# Schematic_SF_1_12_2020_V10.net
KiCad netlist of a schematic drawn in EAGLE
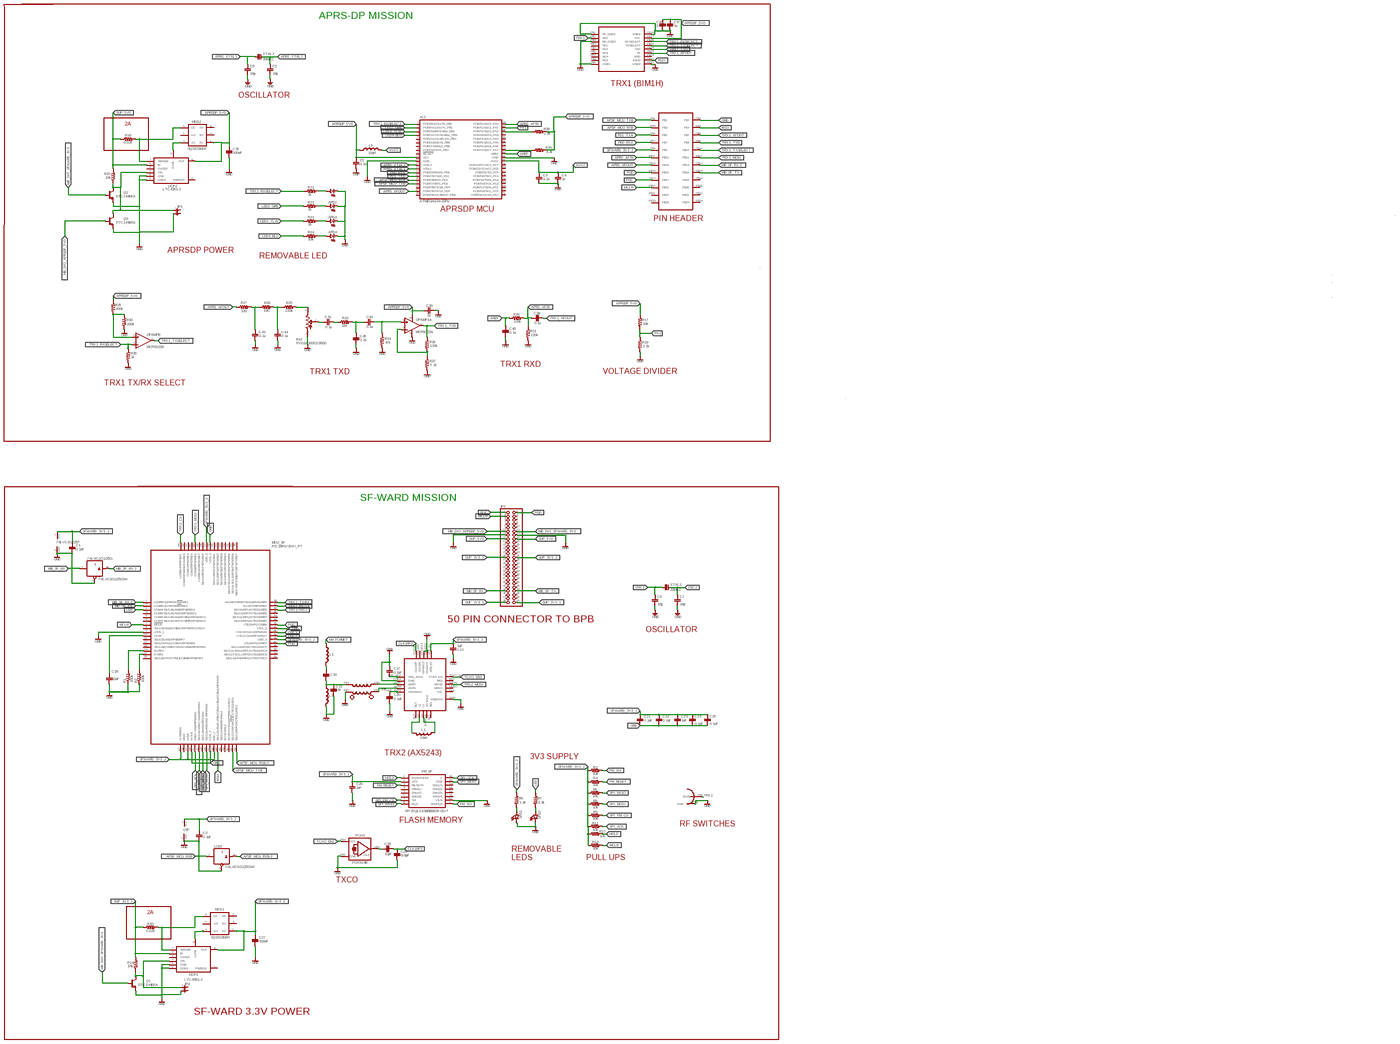
[diagram p0: schematic, sheet 1, overview]
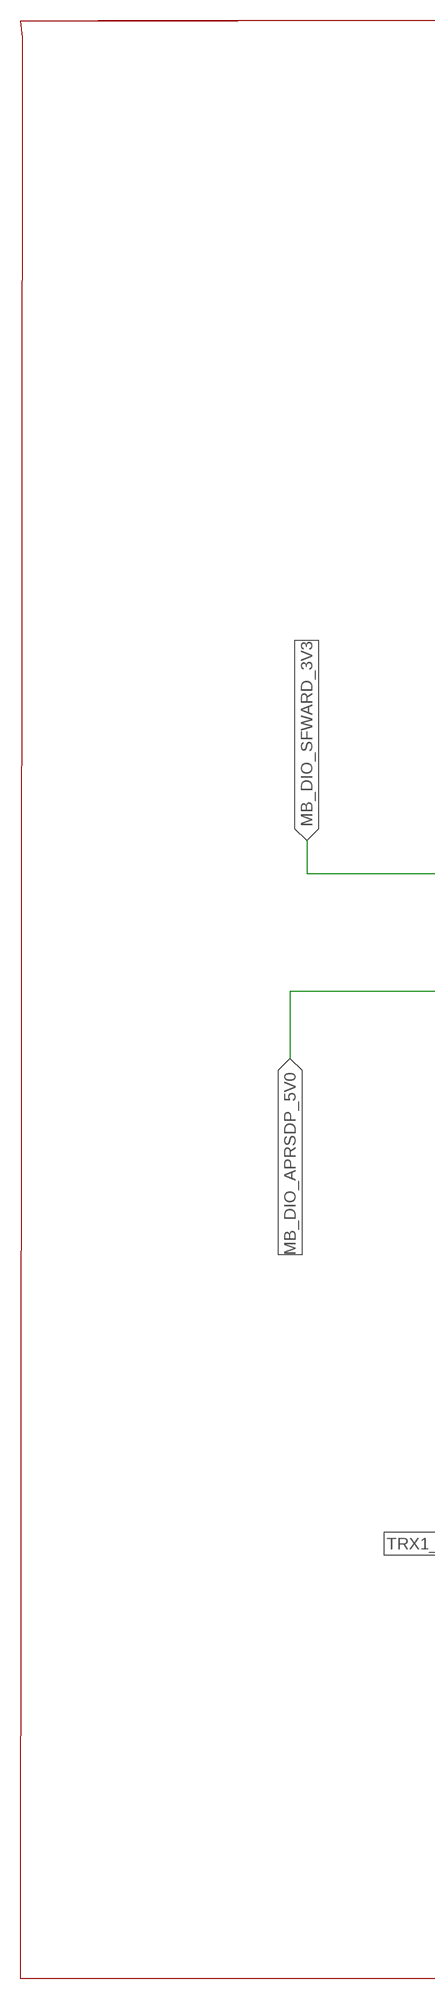
[diagram p1: schematic, sheet 1, part 1 of 4]
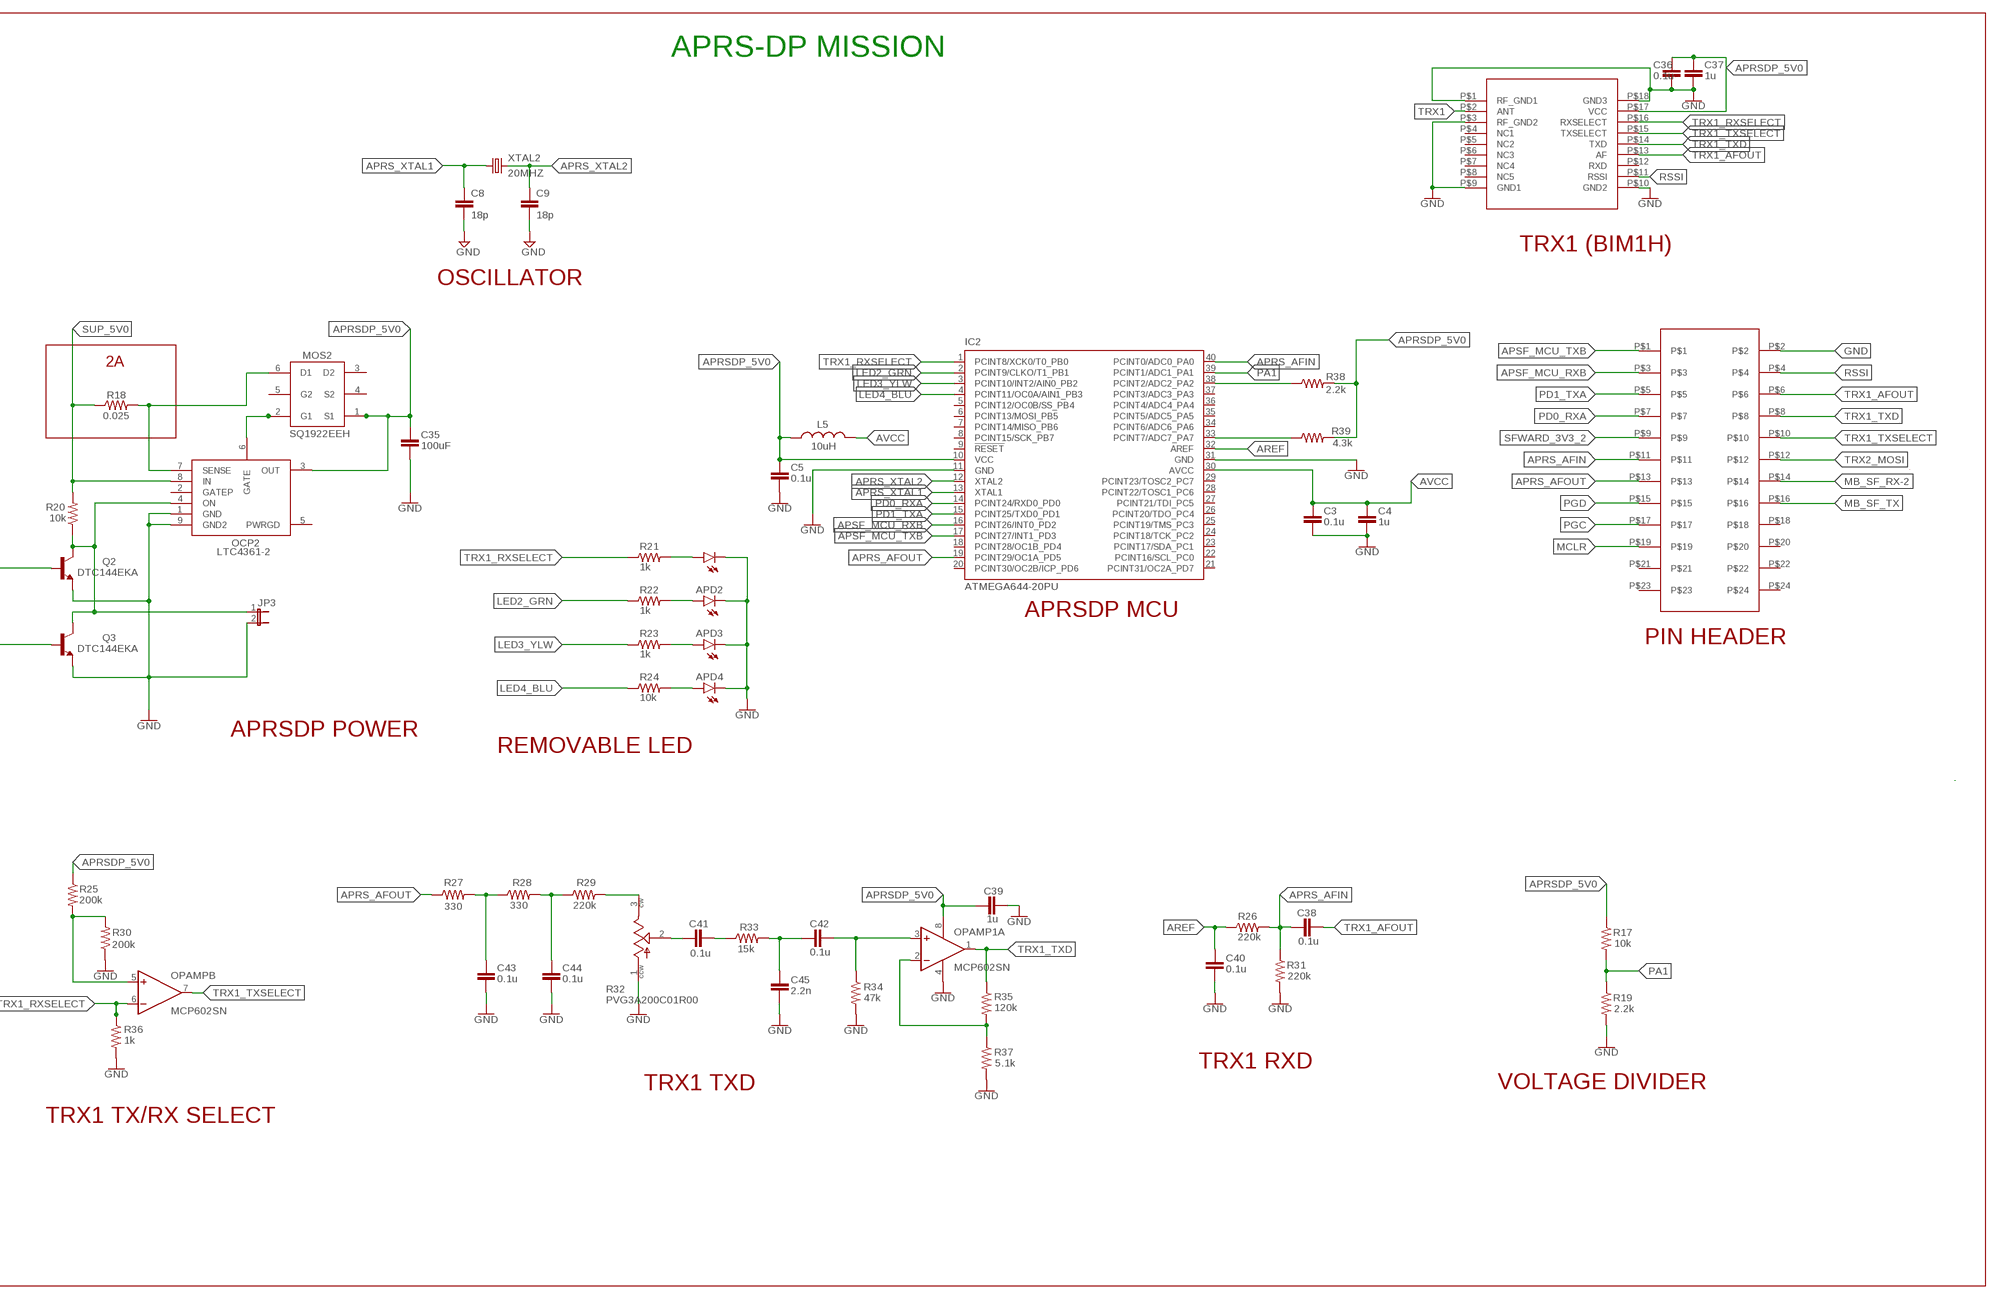
[diagram p2: schematic, sheet 1, part 2 of 4]
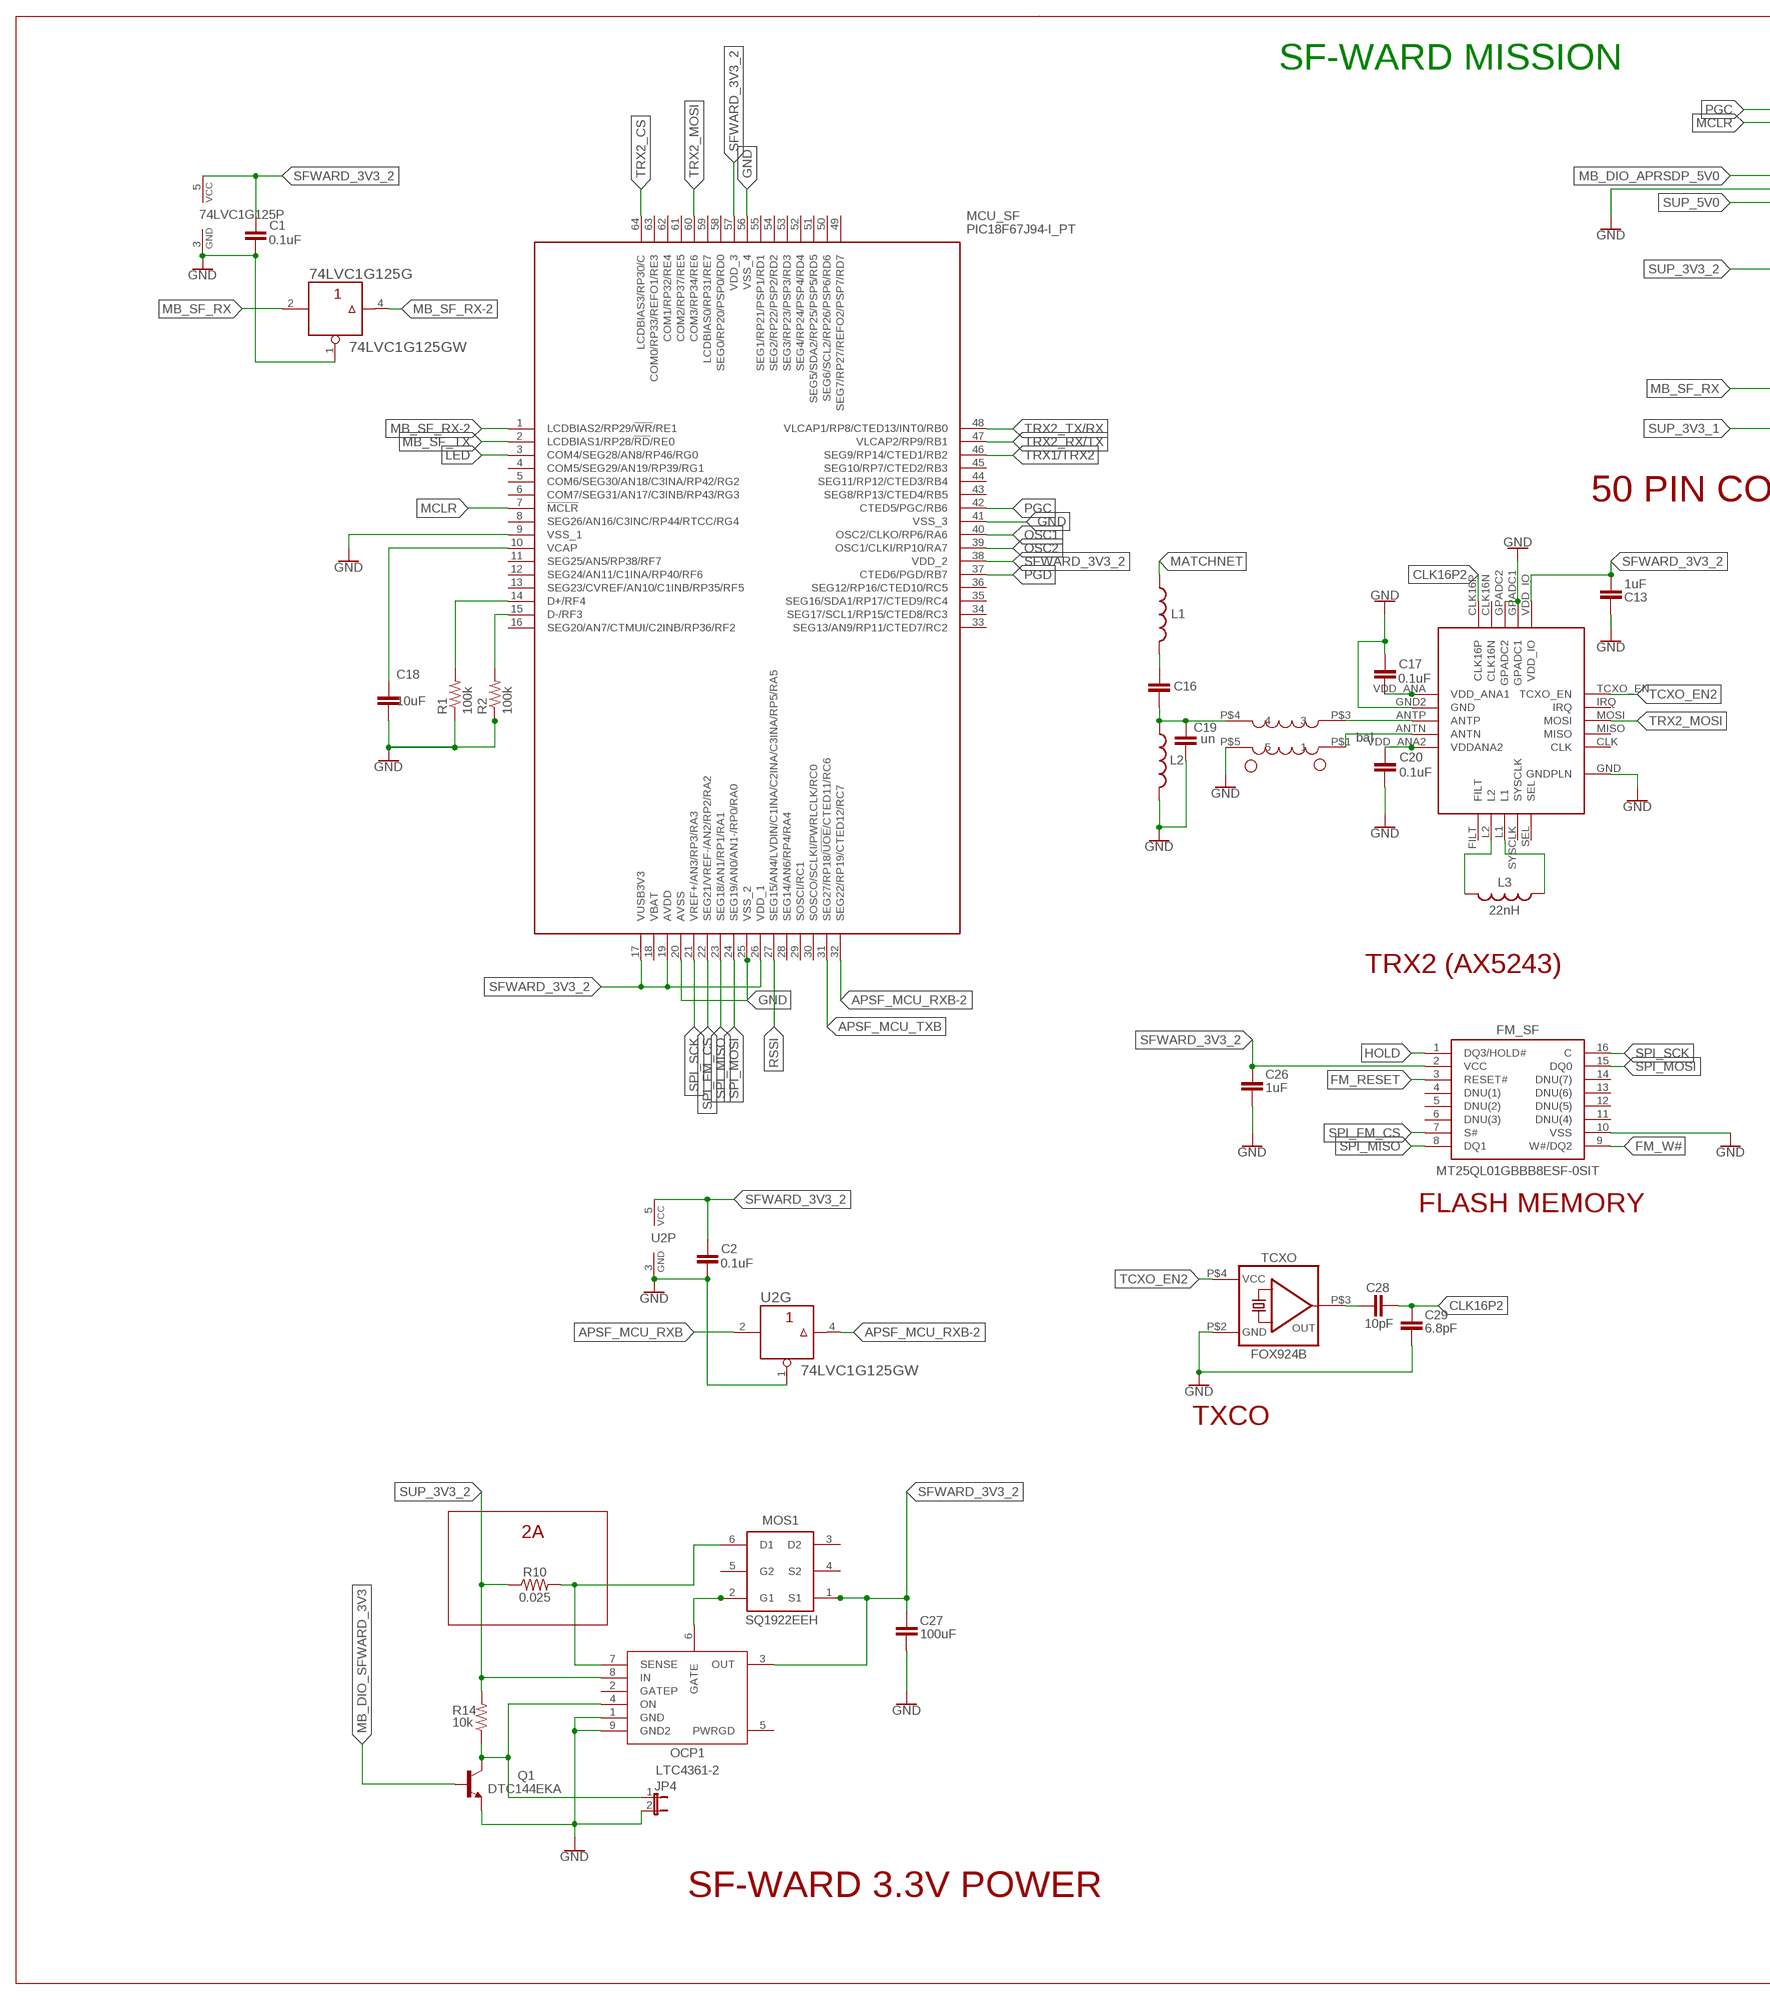
[diagram p3: schematic, sheet 1, part 3 of 4]
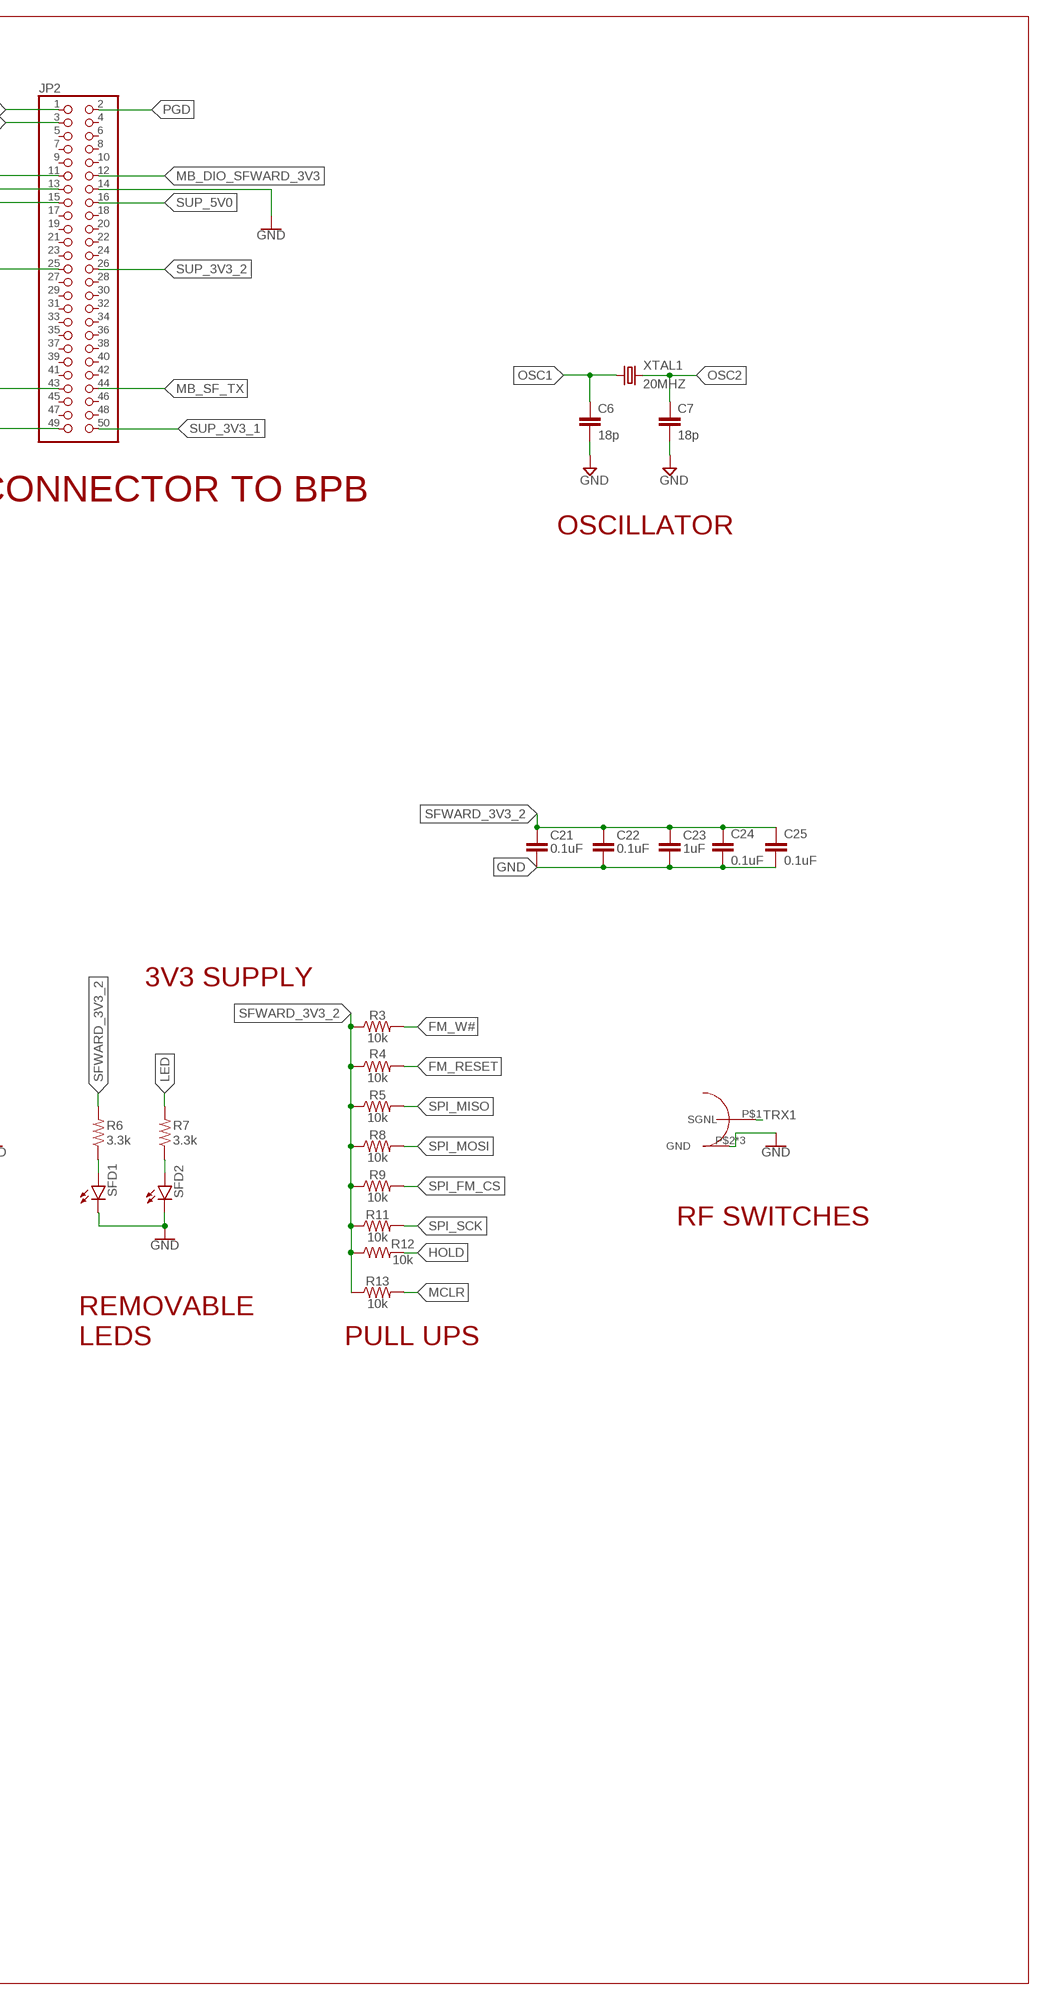
[diagram p4: schematic, sheet 1, part 4 of 4]

(export (version "E")
  (design (tool "Eeschema 10.0.6"))
  (components
    (comp (ref "74LVC1G125")
      (value "74LVC1G125GW")
      (footprint "eagle-import:SOT353-1")
      (libsource (lib "eagle-import") (part "74LVC1G125GW"))
    )
    (comp (ref "APD1")
      (value "LEDSML0603")
      (footprint "eagle-import:SML0603")
      (libsource (lib "eagle-import") (part "LEDSML0603"))
    )
    (comp (ref "APD2")
      (value "LEDSML0603")
      (footprint "eagle-import:SML0603")
      (libsource (lib "eagle-import") (part "LEDSML0603"))
    )
    (comp (ref "APD3")
      (value "LEDSML0603")
      (footprint "eagle-import:SML0603")
      (libsource (lib "eagle-import") (part "LEDSML0603"))
    )
    (comp (ref "APD4")
      (value "LEDSML0603")
      (footprint "eagle-import:SML0603")
      (libsource (lib "eagle-import") (part "LEDSML0603"))
    )
    (comp (ref "BAL")
      (value "MABA-010245-BALUN")
      (footprint "eagle-import:MABA-010245-BALUN")
      (libsource (lib "eagle-import") (part "MABA-010245-BALUN"))
    )
    (comp (ref "C1")
      (value "0.1uF")
      (footprint "eagle-import:C0603")
      (libsource (lib "eagle-import") (part "CC0603"))
    )
    (comp (ref "C2")
      (value "0.1uF")
      (footprint "eagle-import:C0603")
      (libsource (lib "eagle-import") (part "CC0603"))
    )
    (comp (ref "C3")
      (value "0.1u")
      (footprint "eagle-import:C0603")
      (libsource (lib "eagle-import") (part "CC0603"))
    )
    (comp (ref "C4")
      (value "1u")
      (footprint "eagle-import:C0603")
      (libsource (lib "eagle-import") (part "CC0603"))
    )
    (comp (ref "C5")
      (value "0.1u")
      (footprint "eagle-import:C0603")
      (libsource (lib "eagle-import") (part "CC0603"))
    )
    (comp (ref "C6")
      (value "18p")
      (footprint "eagle-import:C0805")
      (libsource (lib "eagle-import") (part "C"))
    )
    (comp (ref "C7")
      (value "18p")
      (footprint "eagle-import:C0805")
      (libsource (lib "eagle-import") (part "C"))
    )
    (comp (ref "C8")
      (value "18p")
      (footprint "eagle-import:C0805")
      (libsource (lib "eagle-import") (part "C"))
    )
    (comp (ref "C9")
      (value "18p")
      (footprint "eagle-import:C0805")
      (libsource (lib "eagle-import") (part "C"))
    )
    (comp (ref "C13")
      (value "1uF")
      (footprint "eagle-import:C0603")
      (libsource (lib "eagle-import") (part "CC0603"))
    )
    (comp (ref "C16")
      (value "C-EUC0805")
      (footprint "eagle-import:C0805")
      (libsource (lib "eagle-import") (part "C-EUC0805"))
    )
    (comp (ref "C17")
      (value "0.1uF")
      (footprint "eagle-import:C0603")
      (libsource (lib "eagle-import") (part "CC0603"))
    )
    (comp (ref "C18")
      (value "10uF")
      (footprint "eagle-import:C0603")
      (libsource (lib "eagle-import") (part "C-EUC0603"))
    )
    (comp (ref "C19")
      (value "C-EUC0805")
      (footprint "eagle-import:C0805")
      (libsource (lib "eagle-import") (part "C-EUC0805"))
    )
    (comp (ref "C20")
      (value "0.1uF")
      (footprint "eagle-import:C0603")
      (libsource (lib "eagle-import") (part "CC0603"))
    )
    (comp (ref "C21")
      (value "0.1uF")
      (footprint "eagle-import:C0603")
      (libsource (lib "eagle-import") (part "C-EUC0603"))
    )
    (comp (ref "C22")
      (value "0.1uF")
      (footprint "eagle-import:C0603")
      (libsource (lib "eagle-import") (part "C-EUC0603"))
    )
    (comp (ref "C23")
      (value "1uF")
      (footprint "eagle-import:C0603")
      (libsource (lib "eagle-import") (part "C-EUC0603"))
    )
    (comp (ref "C24")
      (value "0.1uF")
      (footprint "eagle-import:C0603")
      (libsource (lib "eagle-import") (part "C-EUC0603"))
    )
    (comp (ref "C25")
      (value "0.1uF")
      (footprint "eagle-import:C0603")
      (libsource (lib "eagle-import") (part "C-EUC0603"))
    )
    (comp (ref "C26")
      (value "1uF")
      (footprint "eagle-import:C0603")
      (libsource (lib "eagle-import") (part "C-EUC0603"))
    )
    (comp (ref "C27")
      (value "100uF")
      (footprint "eagle-import:C0805")
      (libsource (lib "eagle-import") (part "C0805(2012)"))
    )
    (comp (ref "C28")
      (value "10pF")
      (footprint "eagle-import:C0603")
      (libsource (lib "eagle-import") (part "CC0603"))
    )
    (comp (ref "C29")
      (value "6.8pF")
      (footprint "eagle-import:C0603")
      (libsource (lib "eagle-import") (part "CC0603"))
    )
    (comp (ref "C35")
      (value "100uF")
      (footprint "eagle-import:C0805")
      (libsource (lib "eagle-import") (part "C0805(2012)"))
    )
    (comp (ref "C36")
      (value "0.1u")
      (footprint "eagle-import:C0603")
      (libsource (lib "eagle-import") (part "CC0603"))
    )
    (comp (ref "C37")
      (value "1u")
      (footprint "eagle-import:C0603")
      (libsource (lib "eagle-import") (part "CC0603"))
    )
    (comp (ref "C38")
      (value "0.1u")
      (footprint "eagle-import:C0603")
      (libsource (lib "eagle-import") (part "CC0603"))
    )
    (comp (ref "C39")
      (value "1u")
      (footprint "eagle-import:C0603")
      (libsource (lib "eagle-import") (part "CC0603"))
    )
    (comp (ref "C40")
      (value "0.1u")
      (footprint "eagle-import:C0603")
      (libsource (lib "eagle-import") (part "CC0603"))
    )
    (comp (ref "C41")
      (value "0.1u")
      (footprint "eagle-import:C0603")
      (libsource (lib "eagle-import") (part "CC0603"))
    )
    (comp (ref "C42")
      (value "0.1u")
      (footprint "eagle-import:C0603")
      (libsource (lib "eagle-import") (part "CC0603"))
    )
    (comp (ref "C43")
      (value "0.1u")
      (footprint "eagle-import:C0603")
      (libsource (lib "eagle-import") (part "CC0603"))
    )
    (comp (ref "C44")
      (value "0.1u")
      (footprint "eagle-import:C0603")
      (libsource (lib "eagle-import") (part "CC0603"))
    )
    (comp (ref "C45")
      (value "2.2n")
      (footprint "eagle-import:C0603")
      (libsource (lib "eagle-import") (part "CC0603"))
    )
    (comp (ref "FM_SF")
      (value "MT25QL01GBBB8ESF-0SIT")
      (footprint "eagle-import:SOIC127P1032X265-16N")
      (libsource (lib "eagle-import") (part "MT25QL01GBBB8ESF-0SIT"))
    )
    (comp (ref "IC2")
      (value "ATMEGA644-20PU")
      (footprint "eagle-import:DIL40")
      (libsource (lib "eagle-import") (part "ATMEGA644-PU20"))
    )
    (comp (ref "JP1")
      (value "RAB_ACCESS")
      (footprint "eagle-import:RAB_ACCESS")
      (libsource (lib "eagle-import") (part "RAB_ACCESS"))
    )
    (comp (ref "JP2")
      (value "PINHD-2X25_2.00")
      (footprint "eagle-import:2X25M")
      (libsource (lib "eagle-import") (part "PINHD-2X25_2.00"))
    )
    (comp (ref "JP3")
      (value "JP1E")
      (footprint "eagle-import:JP1")
      (libsource (lib "eagle-import") (part "JP1E"))
    )
    (comp (ref "JP4")
      (value "JP1E")
      (footprint "eagle-import:JP1")
      (libsource (lib "eagle-import") (part "JP1E"))
    )
    (comp (ref "L1")
      (value "L-USL2012C")
      (footprint "eagle-import:L2012C")
      (libsource (lib "eagle-import") (part "L-USL2012C"))
    )
    (comp (ref "L2")
      (value "L-USL2012C")
      (footprint "eagle-import:L2012C")
      (libsource (lib "eagle-import") (part "L-USL2012C"))
    )
    (comp (ref "L3")
      (value "22nH")
      (footprint "eagle-import:L2012C")
      (libsource (lib "eagle-import") (part "L-USL2012C"))
    )
    (comp (ref "L5")
      (value "10uH")
      (footprint "eagle-import:L2012C")
      (libsource (lib "eagle-import") (part "L-USL2012C"))
    )
    (comp (ref "MCU_SF")
      (value "PIC18F67J94-I_PT")
      (footprint "eagle-import:QFP50P1200X1200X120-64N")
      (fields
        (field (name "MANUFACTURER_PART_NUMBER") "PIC18F67J94-I/PT")
        (field (name "MOUSER_PART_NUMBER") "579-PIC18F67J94-I/PT")
        (field (name "RS_PART_NUMBER") "1652172")
      )
      (libsource (lib "eagle-import") (part "PIC18F67J94-I_PT"))
    )
    (comp (ref "MMCX_908_222101T")
      (value "MMCX_908_222101T")
      (footprint "eagle-import:MMCX_908_222101T")
      (libsource (lib "eagle-import") (part "MMCX_908_222101T"))
    )
    (comp (ref "MOS1")
      (value "SQ1922EEH")
      (footprint "eagle-import:SOT65P210X110-6N")
      (libsource (lib "eagle-import") (part "SQ1922EEH"))
    )
    (comp (ref "MOS2")
      (value "SQ1922EEH")
      (footprint "eagle-import:SOT65P210X110-6N")
      (libsource (lib "eagle-import") (part "SQ1922EEH"))
    )
    (comp (ref "OCP1")
      (value "LTC4361-2")
      (footprint "eagle-import:DFN")
      (libsource (lib "eagle-import") (part "LTC4361-2"))
    )
    (comp (ref "OCP2")
      (value "LTC4361-2")
      (footprint "eagle-import:DFN")
      (libsource (lib "eagle-import") (part "LTC4361-2"))
    )
    (comp (ref "OPAMP")
      (value "MCP602SN")
      (footprint "eagle-import:SO08")
      (libsource (lib "eagle-import") (part "MCP602SN"))
    )
    (comp (ref "OPAMP1")
      (value "MCP602SN")
      (footprint "eagle-import:SO08")
      (libsource (lib "eagle-import") (part "MCP602SN"))
    )
    (comp (ref "Q1")
      (value "DTC144EKA")
      (footprint "eagle-import:SOT346-R")
      (libsource (lib "eagle-import") (part "DTC144EKA"))
    )
    (comp (ref "Q2")
      (value "DTC144EKA")
      (footprint "eagle-import:SOT346-R")
      (libsource (lib "eagle-import") (part "DTC144EKA"))
    )
    (comp (ref "Q3")
      (value "DTC144EKA")
      (footprint "eagle-import:SOT346-R")
      (libsource (lib "eagle-import") (part "DTC144EKA"))
    )
    (comp (ref "R1")
      (value "100k")
      (footprint "eagle-import:R0603")
      (libsource (lib "eagle-import") (part "R-US_R0603"))
    )
    (comp (ref "R2")
      (value "100k")
      (footprint "eagle-import:R0603")
      (libsource (lib "eagle-import") (part "R-US_R0603"))
    )
    (comp (ref "R3")
      (value "10k")
      (footprint "eagle-import:R0603")
      (libsource (lib "eagle-import") (part "R-US_R0603"))
    )
    (comp (ref "R4")
      (value "10k")
      (footprint "eagle-import:R0603")
      (libsource (lib "eagle-import") (part "R-US_R0603"))
    )
    (comp (ref "R5")
      (value "10k")
      (footprint "eagle-import:R0603")
      (libsource (lib "eagle-import") (part "R-US_R0603"))
    )
    (comp (ref "R6")
      (value "3.3k")
      (footprint "eagle-import:R0603")
      (libsource (lib "eagle-import") (part "R-US_R0603"))
    )
    (comp (ref "R7")
      (value "3.3k")
      (footprint "eagle-import:R0603")
      (libsource (lib "eagle-import") (part "R-US_R0603"))
    )
    (comp (ref "R8")
      (value "10k")
      (footprint "eagle-import:R0603")
      (libsource (lib "eagle-import") (part "R-US_R0603"))
    )
    (comp (ref "R9")
      (value "10k")
      (footprint "eagle-import:R0603")
      (libsource (lib "eagle-import") (part "R-US_R0603"))
    )
    (comp (ref "R10")
      (value "0.025")
      (footprint "eagle-import:R0805")
      (libsource (lib "eagle-import") (part "R0805(2012)"))
    )
    (comp (ref "R11")
      (value "10k")
      (footprint "eagle-import:R0603")
      (libsource (lib "eagle-import") (part "R-US_R0603"))
    )
    (comp (ref "R12")
      (value "10k")
      (footprint "eagle-import:R0603")
      (libsource (lib "eagle-import") (part "R-US_R0603"))
    )
    (comp (ref "R13")
      (value "10k")
      (footprint "eagle-import:R0603")
      (libsource (lib "eagle-import") (part "R-US_R0603"))
    )
    (comp (ref "R14")
      (value "10k")
      (footprint "eagle-import:R0603")
      (libsource (lib "eagle-import") (part "R-US_R0603"))
    )
    (comp (ref "R17")
      (value "10k")
      (footprint "eagle-import:R0603")
      (libsource (lib "eagle-import") (part "R-US_R0603"))
    )
    (comp (ref "R18")
      (value "0.025")
      (footprint "eagle-import:R0805")
      (libsource (lib "eagle-import") (part "R-US_R0805"))
    )
    (comp (ref "R19")
      (value "2.2k")
      (footprint "eagle-import:R0603")
      (libsource (lib "eagle-import") (part "R-US_R0603"))
    )
    (comp (ref "R20")
      (value "10k")
      (footprint "eagle-import:R0603")
      (libsource (lib "eagle-import") (part "R-US_R0603"))
    )
    (comp (ref "R21")
      (value "1k")
      (footprint "eagle-import:R0603")
      (libsource (lib "eagle-import") (part "R-US_R0603"))
    )
    (comp (ref "R22")
      (value "1k")
      (footprint "eagle-import:R0603")
      (libsource (lib "eagle-import") (part "R-US_R0603"))
    )
    (comp (ref "R23")
      (value "1k")
      (footprint "eagle-import:R0603")
      (libsource (lib "eagle-import") (part "R-US_R0603"))
    )
    (comp (ref "R24")
      (value "10k")
      (footprint "eagle-import:R0603")
      (libsource (lib "eagle-import") (part "R-US_R0603"))
    )
    (comp (ref "R25")
      (value "200k")
      (footprint "eagle-import:R0603")
      (libsource (lib "eagle-import") (part "R-US_R0603"))
    )
    (comp (ref "R26")
      (value "220k")
      (footprint "eagle-import:R0603")
      (libsource (lib "eagle-import") (part "R-US_R0603"))
    )
    (comp (ref "R27")
      (value "330")
      (footprint "eagle-import:R0603")
      (libsource (lib "eagle-import") (part "R-US_R0603"))
    )
    (comp (ref "R28")
      (value "330")
      (footprint "eagle-import:R0603")
      (libsource (lib "eagle-import") (part "R-US_R0603"))
    )
    (comp (ref "R29")
      (value "220k")
      (footprint "eagle-import:R0603")
      (libsource (lib "eagle-import") (part "R-US_R0603"))
    )
    (comp (ref "R30")
      (value "200k")
      (footprint "eagle-import:R0603")
      (libsource (lib "eagle-import") (part "R-US_R0603"))
    )
    (comp (ref "R31")
      (value "220k")
      (footprint "eagle-import:R0603")
      (libsource (lib "eagle-import") (part "R-US_R0603"))
    )
    (comp (ref "R32")
      (value "PVG3A200C01R00")
      (footprint "eagle-import:TRIM_PVG3A200C01R00")
      (fields (field (name "DIGI-KEY_PART_NUMBER") "490-2647-1-ND") (field (name "MF") "Bourns"))
      (libsource (lib "eagle-import") (part "PVG3A200C01R00"))
    )
    (comp (ref "R33")
      (value "15k")
      (footprint "eagle-import:R0603")
      (libsource (lib "eagle-import") (part "R-US_R0603"))
    )
    (comp (ref "R34")
      (value "47k")
      (footprint "eagle-import:R0603")
      (libsource (lib "eagle-import") (part "R-US_R0603"))
    )
    (comp (ref "R35")
      (value "120k")
      (footprint "eagle-import:R0603")
      (libsource (lib "eagle-import") (part "R-US_R0603"))
    )
    (comp (ref "R36")
      (value "1k")
      (footprint "eagle-import:R0603")
      (libsource (lib "eagle-import") (part "R-US_R0603"))
    )
    (comp (ref "R37")
      (value "5.1k")
      (footprint "eagle-import:R0603")
      (libsource (lib "eagle-import") (part "R-US_R0603"))
    )
    (comp (ref "R38")
      (value "2.2k")
      (footprint "eagle-import:R0603")
      (libsource (lib "eagle-import") (part "R-US_R0603"))
    )
    (comp (ref "R39")
      (value "4.3k")
      (footprint "eagle-import:R0603")
      (libsource (lib "eagle-import") (part "R-US_R0603"))
    )
    (comp (ref "SFD1")
      (value "LEDCHIPLED_0603")
      (footprint "eagle-import:CHIPLED_0603")
      (libsource (lib "eagle-import") (part "LEDCHIPLED_0603"))
    )
    (comp (ref "SFD2")
      (value "LEDCHIPLED_0603")
      (footprint "eagle-import:CHIPLED_0603")
      (libsource (lib "eagle-import") (part "LEDCHIPLED_0603"))
    )
    (comp (ref "TCXO")
      (value "FOX924B")
      (footprint "eagle-import:FOX924B")
      (libsource (lib "eagle-import") (part "FOX924B"))
    )
    (comp (ref "TRX1")
      (value "BIM1H")
      (footprint "eagle-import:BIM1H")
      (libsource (lib "eagle-import") (part "BIM1H"))
    )
    (comp (ref "TRX2")
      (value "AX5243")
      (footprint "eagle-import:AX5243")
      (libsource (lib "eagle-import") (part "AX5243"))
    )
    (comp (ref "U2")
      (value "74LVC1G125GW")
      (footprint "eagle-import:SOT353-1")
      (libsource (lib "eagle-import") (part "74LVC1G125GW"))
    )
    (comp (ref "XTAL1")
      (value "20MHZ")
      (footprint "eagle-import:SM49")
      (libsource (lib "eagle-import") (part "CRYSTALSM49"))
    )
    (comp (ref "XTAL2")
      (value "20MHZ")
      (footprint "eagle-import:SM49")
      (libsource (lib "eagle-import") (part "CRYSTALSM49"))
    )
  )
  (nets
    (net (code "1") (name "APRSDP_5V0") (class "Default")
      (node (ref "C35") (pin "1") (pinfunction "1_1") (pintype "passive"))
      (node (ref "C36") (pin "1") (pinfunction "1_1") (pintype "passive"))
      (node (ref "C37") (pin "1") (pinfunction "1_1") (pintype "passive"))
      (node (ref "C39") (pin "1") (pinfunction "1_1") (pintype "passive"))
      (node (ref "C5") (pin "2") (pinfunction "2_2") (pintype "passive"))
      (node (ref "IC2") (pin "10") (pinfunction "VCC_10") (pintype "power_in"))
      (node (ref "L5") (pin "1") (pinfunction "1_1") (pintype "passive"))
      (node (ref "MOS2") (pin "1") (pinfunction "S1_1") (pintype "input"))
      (node (ref "OCP2") (pin "3") (pinfunction "OUT_3") (pintype "bidirectional"))
      (node (ref "OPAMP1") (pin "8") (pinfunction "V+_8") (pintype "power_in"))
      (node (ref "R17") (pin "1") (pinfunction "1_1") (pintype "passive"))
      (node (ref "R25") (pin "1") (pinfunction "1_1") (pintype "passive"))
      (node (ref "R38") (pin "2") (pinfunction "2_2") (pintype "passive"))
      (node (ref "R39") (pin "2") (pinfunction "2_2") (pintype "passive"))
      (node (ref "TRX1") (pin "P$17") (pinfunction "VCC_P$17") (pintype "bidirectional"))
    )
    (net (code "2") (name "APRS_AFIN") (class "Default")
      (node (ref "C38") (pin "1") (pinfunction "1_1") (pintype "passive"))
      (node (ref "IC2") (pin "40") (pinfunction "PCINT0/ADC0_PA0_40") (pintype "bidirectional"))
      (node (ref "JP1") (pin "P$11") (pinfunction "P$11_P$11") (pintype "bidirectional"))
      (node (ref "R26") (pin "2") (pinfunction "2_2") (pintype "passive"))
      (node (ref "R31") (pin "1") (pinfunction "1_1") (pintype "passive"))
    )
    (net (code "3") (name "APRS_AFOUT") (class "Default")
      (node (ref "IC2") (pin "19") (pinfunction "PCINT29/OC1A_PD5_19") (pintype "bidirectional"))
      (node (ref "JP1") (pin "P$13") (pinfunction "P$13_P$13") (pintype "bidirectional"))
      (node (ref "R27") (pin "1") (pinfunction "1_1") (pintype "passive"))
    )
    (net (code "4") (name "APRS_XTAL1") (class "Default")
      (node (ref "C8") (pin "1") (pinfunction "1_1") (pintype "passive"))
      (node (ref "IC2") (pin "13") (pinfunction "XTAL1_13") (pintype "input"))
      (node (ref "XTAL2") (pin "1") (pinfunction "1_1") (pintype "passive"))
    )
    (net (code "5") (name "APRS_XTAL2") (class "Default")
      (node (ref "C9") (pin "1") (pinfunction "1_1") (pintype "passive"))
      (node (ref "IC2") (pin "12") (pinfunction "XTAL2_12") (pintype "output"))
      (node (ref "XTAL2") (pin "2") (pinfunction "2_2") (pintype "passive"))
    )
    (net (code "6") (name "APSF_MCU_RXB") (class "Default")
      (node (ref "IC2") (pin "16") (pinfunction "PCINT26/INT0_PD2_16") (pintype "bidirectional"))
      (node (ref "JP1") (pin "P$3") (pinfunction "P$3_P$3") (pintype "bidirectional"))
      (node (ref "U2") (pin "2") (pinfunction "A_2") (pintype "input"))
    )
    (net (code "7") (name "APSF_MCU_RXB-2") (class "Default")
      (node (ref "MCU_SF") (pin "32") (pinfunction "SEG22/RP19/CTED12/RC7_32") (pintype "bidirectional"))
      (node (ref "U2") (pin "4") (pinfunction "Y_4") (pintype "output"))
    )
    (net (code "8") (name "APSF_MCU_TXB") (class "Default")
      (node (ref "IC2") (pin "17") (pinfunction "PCINT27/INT1_PD3_17") (pintype "bidirectional"))
      (node (ref "JP1") (pin "P$1") (pinfunction "P$1_P$1") (pintype "bidirectional"))
      (node (ref "MCU_SF") (pin "31") (pinfunction "SEG27/RP18/~{UOE}/CTED11/RC6_31") (pintype "bidirectional"))
    )
    (net (code "9") (name "AREF") (class "Default")
      (node (ref "C40") (pin "1") (pinfunction "1_1") (pintype "passive"))
      (node (ref "IC2") (pin "32") (pinfunction "AREF_32") (pintype "passive"))
      (node (ref "R26") (pin "1") (pinfunction "1_1") (pintype "passive"))
    )
    (net (code "10") (name "AVCC") (class "Default")
      (node (ref "C3") (pin "1") (pinfunction "1_1") (pintype "passive"))
      (node (ref "C4") (pin "1") (pinfunction "1_1") (pintype "passive"))
      (node (ref "IC2") (pin "30") (pinfunction "AVCC_30") (pintype "power_in"))
      (node (ref "L5") (pin "2") (pinfunction "2_2") (pintype "passive"))
    )
    (net (code "11") (name "CLK16P2") (class "Default")
      (node (ref "C28") (pin "2") (pinfunction "2_2") (pintype "passive"))
      (node (ref "C29") (pin "1") (pinfunction "1_1") (pintype "passive"))
      (node (ref "TRX2") (pin "CLK16P") (pinfunction "CLK16P_CLK16P") (pintype "bidirectional"))
    )
    (net (code "12") (name "FM_RESET") (class "Default")
      (node (ref "FM_SF") (pin "3") (pinfunction "RESET#_3") (pintype "input"))
      (node (ref "R4") (pin "2") (pinfunction "2_2") (pintype "passive"))
    )
    (net (code "13") (name "FM_W#") (class "Default")
      (node (ref "FM_SF") (pin "9") (pinfunction "W#/DQ2_9") (pintype "input"))
      (node (ref "R3") (pin "2") (pinfunction "2_2") (pintype "passive"))
    )
    (net (code "14") (name "GND") (class "Default")
      (node (ref "74LVC1G125") (pin "1") (pinfunction "OEN_1") (pintype "input"))
      (node (ref "74LVC1G125") (pin "3") (pinfunction "GND_3") (pintype "power_in"))
      (node (ref "APD1") (pin "C") (pinfunction "C_C") (pintype "passive"))
      (node (ref "APD2") (pin "C") (pinfunction "C_C") (pintype "passive"))
      (node (ref "APD3") (pin "C") (pinfunction "C_C") (pintype "passive"))
      (node (ref "APD4") (pin "C") (pinfunction "C_C") (pintype "passive"))
      (node (ref "BAL") (pin "P$5") (pinfunction "5_P$5") (pintype "bidirectional"))
      (node (ref "C1") (pin "1") (pinfunction "1_1") (pintype "passive"))
      (node (ref "C13") (pin "1") (pinfunction "1_1") (pintype "passive"))
      (node (ref "C17") (pin "2") (pinfunction "2_2") (pintype "passive"))
      (node (ref "C18") (pin "2") (pinfunction "2_2") (pintype "passive"))
      (node (ref "C19") (pin "2") (pinfunction "2_2") (pintype "passive"))
      (node (ref "C2") (pin "1") (pinfunction "1_1") (pintype "passive"))
      (node (ref "C20") (pin "2") (pinfunction "2_2") (pintype "passive"))
      (node (ref "C21") (pin "2") (pinfunction "2_2") (pintype "passive"))
      (node (ref "C22") (pin "2") (pinfunction "2_2") (pintype "passive"))
      (node (ref "C23") (pin "2") (pinfunction "2_2") (pintype "passive"))
      (node (ref "C24") (pin "2") (pinfunction "2_2") (pintype "passive"))
      (node (ref "C25") (pin "2") (pinfunction "2_2") (pintype "passive"))
      (node (ref "C26") (pin "2") (pinfunction "2_2") (pintype "passive"))
      (node (ref "C27") (pin "2") (pinfunction "2_2") (pintype "passive"))
      (node (ref "C29") (pin "2") (pinfunction "2_2") (pintype "passive"))
      (node (ref "C3") (pin "2") (pinfunction "2_2") (pintype "passive"))
      (node (ref "C35") (pin "2") (pinfunction "2_2") (pintype "passive"))
      (node (ref "C36") (pin "2") (pinfunction "2_2") (pintype "passive"))
      (node (ref "C37") (pin "2") (pinfunction "2_2") (pintype "passive"))
      (node (ref "C39") (pin "2") (pinfunction "2_2") (pintype "passive"))
      (node (ref "C4") (pin "2") (pinfunction "2_2") (pintype "passive"))
      (node (ref "C40") (pin "2") (pinfunction "2_2") (pintype "passive"))
      (node (ref "C43") (pin "2") (pinfunction "2_2") (pintype "passive"))
      (node (ref "C44") (pin "2") (pinfunction "2_2") (pintype "passive"))
      (node (ref "C45") (pin "2") (pinfunction "2_2") (pintype "passive"))
      (node (ref "C5") (pin "1") (pinfunction "1_1") (pintype "passive"))
      (node (ref "C6") (pin "2") (pinfunction "2_2") (pintype "passive"))
      (node (ref "C7") (pin "2") (pinfunction "2_2") (pintype "passive"))
      (node (ref "C8") (pin "2") (pinfunction "2_2") (pintype "passive"))
      (node (ref "C9") (pin "2") (pinfunction "2_2") (pintype "passive"))
      (node (ref "FM_SF") (pin "10") (pinfunction "VSS_10") (pintype "input"))
      (node (ref "IC2") (pin "11") (pinfunction "GND_11") (pintype "power_in"))
      (node (ref "IC2") (pin "31") (pinfunction "GND_31") (pintype "power_in"))
      (node (ref "JP1") (pin "P$2") (pinfunction "P$2_P$2") (pintype "bidirectional"))
      (node (ref "JP2") (pin "13") (pinfunction "13_13") (pintype "passive"))
      (node (ref "JP2") (pin "14") (pinfunction "14_14") (pintype "passive"))
      (node (ref "JP3") (pin "2") (pinfunction "2_2") (pintype "passive"))
      (node (ref "JP4") (pin "2") (pinfunction "2_2") (pintype "passive"))
      (node (ref "L2") (pin "2") (pinfunction "2_2") (pintype "passive"))
      (node (ref "MCU_SF") (pin "20") (pinfunction "AVSS_20") (pintype "bidirectional"))
      (node (ref "MCU_SF") (pin "25") (pinfunction "VSS_2_25") (pintype "bidirectional"))
      (node (ref "MCU_SF") (pin "41") (pinfunction "VSS_3_41") (pintype "bidirectional"))
      (node (ref "MCU_SF") (pin "56") (pinfunction "VSS_4_56") (pintype "bidirectional"))
      (node (ref "MCU_SF") (pin "9") (pinfunction "VSS_1_9") (pintype "bidirectional"))
      (node (ref "MMCX_908_222101T") (pin "P$2") (pinfunction "GND_P$2") (pintype "bidirectional"))
      (node (ref "MMCX_908_222101T") (pin "P$3") (pinfunction "GND_P$3") (pintype "bidirectional"))
      (node (ref "MMCX_908_222101T") (pin "P$4") (pinfunction "GND_P$4") (pintype "bidirectional"))
      (node (ref "OCP1") (pin "1") (pinfunction "GND_1") (pintype "bidirectional"))
      (node (ref "OCP1") (pin "9") (pinfunction "GND2_9") (pintype "bidirectional"))
      (node (ref "OCP2") (pin "1") (pinfunction "GND_1") (pintype "bidirectional"))
      (node (ref "OCP2") (pin "9") (pinfunction "GND2_9") (pintype "bidirectional"))
      (node (ref "OPAMP1") (pin "4") (pinfunction "V-_4") (pintype "power_in"))
      (node (ref "Q1") (pin "1") (pinfunction "E_1") (pintype "passive"))
      (node (ref "Q2") (pin "1") (pinfunction "E_1") (pintype "passive"))
      (node (ref "Q3") (pin "1") (pinfunction "E_1") (pintype "passive"))
      (node (ref "R1") (pin "1") (pinfunction "1_1") (pintype "passive"))
      (node (ref "R19") (pin "2") (pinfunction "2_2") (pintype "passive"))
      (node (ref "R2") (pin "1") (pinfunction "1_1") (pintype "passive"))
      (node (ref "R30") (pin "1") (pinfunction "1_1") (pintype "passive"))
      (node (ref "R31") (pin "2") (pinfunction "2_2") (pintype "passive"))
      (node (ref "R32") (pin "1") (pinfunction "CCW_1") (pintype "passive"))
      (node (ref "R34") (pin "2") (pinfunction "2_2") (pintype "passive"))
      (node (ref "R36") (pin "2") (pinfunction "2_2") (pintype "passive"))
      (node (ref "R37") (pin "2") (pinfunction "2_2") (pintype "passive"))
      (node (ref "SFD1") (pin "C") (pinfunction "C_C") (pintype "passive"))
      (node (ref "SFD2") (pin "C") (pinfunction "C_C") (pintype "passive"))
      (node (ref "TCXO") (pin "P$2") (pinfunction "GND_P$2") (pintype "power_in"))
      (node (ref "TRX1") (pin "P$1") (pinfunction "RF_GND1_P$1") (pintype "bidirectional"))
      (node (ref "TRX1") (pin "P$10") (pinfunction "GND2_P$10") (pintype "bidirectional"))
      (node (ref "TRX1") (pin "P$18") (pinfunction "GND3_P$18") (pintype "bidirectional"))
      (node (ref "TRX1") (pin "P$3") (pinfunction "RF_GND2_P$3") (pintype "bidirectional"))
      (node (ref "TRX1") (pin "P$9") (pinfunction "GND1_P$9") (pintype "bidirectional"))
      (node (ref "TRX2") (pin "GND") (pinfunction "GNDPLN_GND") (pintype "bidirectional"))
      (node (ref "TRX2") (pin "GND2") (pinfunction "GND_GND2") (pintype "bidirectional"))
      (node (ref "TRX2") (pin "GPADC1") (pinfunction "GPADC1_GPADC1") (pintype "bidirectional"))
      (node (ref "TRX2") (pin "GPADC2") (pinfunction "GPADC2_GPADC2") (pintype "bidirectional"))
      (node (ref "U2") (pin "1") (pinfunction "OEN_1") (pintype "input"))
      (node (ref "U2") (pin "3") (pinfunction "GND_3") (pintype "power_in"))
    )
    (net (code "15") (name "HOLD") (class "Default")
      (node (ref "FM_SF") (pin "1") (pinfunction "DQ3/HOLD#_1") (pintype "input"))
      (node (ref "R12") (pin "2") (pinfunction "2_2") (pintype "passive"))
    )
    (net (code "16") (name "LED") (class "Default")
      (node (ref "MCU_SF") (pin "3") (pinfunction "COM4/SEG28/AN8/RP46/RG0_3") (pintype "bidirectional"))
      (node (ref "R7") (pin "2") (pinfunction "2_2") (pintype "passive"))
    )
    (net (code "17") (name "LED2_GRN") (class "Default")
      (node (ref "IC2") (pin "2") (pinfunction "PCINT9/CLKO/T1_PB1_2") (pintype "bidirectional"))
      (node (ref "R22") (pin "1") (pinfunction "1_1") (pintype "passive"))
    )
    (net (code "18") (name "LED3_YLW") (class "Default")
      (node (ref "IC2") (pin "3") (pinfunction "PCINT10/INT2/AIN0_PB2_3") (pintype "bidirectional"))
      (node (ref "R23") (pin "1") (pinfunction "1_1") (pintype "passive"))
    )
    (net (code "19") (name "LED4_BLU") (class "Default")
      (node (ref "IC2") (pin "4") (pinfunction "PCINT11/OC0A/AIN1_PB3_4") (pintype "bidirectional"))
      (node (ref "R24") (pin "1") (pinfunction "1_1") (pintype "passive"))
    )
    (net (code "20") (name "MATCHNET") (class "Default")
      (node (ref "L1") (pin "1") (pinfunction "1_1") (pintype "passive"))
    )
    (net (code "21") (name "MB_DIO_APRSDP_5V0") (class "Default")
      (node (ref "JP2") (pin "11") (pinfunction "11_11") (pintype "passive"))
      (node (ref "Q3") (pin "2") (pinfunction "B_2") (pintype "passive"))
    )
    (net (code "22") (name "MB_DIO_SFWARD_3V3") (class "Default")
      (node (ref "JP2") (pin "12") (pinfunction "12_12") (pintype "passive"))
      (node (ref "Q1") (pin "2") (pinfunction "B_2") (pintype "passive"))
      (node (ref "Q2") (pin "2") (pinfunction "B_2") (pintype "passive"))
    )
    (net (code "23") (name "MB_SF_RX") (class "Default")
      (node (ref "74LVC1G125") (pin "2") (pinfunction "A_2") (pintype "input"))
      (node (ref "JP2") (pin "43") (pinfunction "43_43") (pintype "passive"))
    )
    (net (code "24") (name "MB_SF_RX-2") (class "Default")
      (node (ref "74LVC1G125") (pin "4") (pinfunction "Y_4") (pintype "output"))
      (node (ref "JP1") (pin "P$14") (pinfunction "P$14_P$14") (pintype "bidirectional"))
      (node (ref "MCU_SF") (pin "1") (pinfunction "LCDBIAS2/RP29/~{WR}/RE1_1") (pintype "bidirectional"))
    )
    (net (code "25") (name "MB_SF_TX") (class "Default")
      (node (ref "JP1") (pin "P$16") (pinfunction "P$16_P$16") (pintype "bidirectional"))
      (node (ref "JP2") (pin "44") (pinfunction "44_44") (pintype "passive"))
      (node (ref "MCU_SF") (pin "2") (pinfunction "LCDBIAS1/RP28/~{RD}/RE0_2") (pintype "bidirectional"))
    )
    (net (code "26") (name "MCLR") (class "Default")
      (node (ref "JP1") (pin "P$19") (pinfunction "P$19_P$19") (pintype "bidirectional"))
      (node (ref "JP2") (pin "3") (pinfunction "3_3") (pintype "passive"))
      (node (ref "MCU_SF") (pin "7") (pinfunction "~{MCLR}_7") (pintype "bidirectional"))
      (node (ref "R13") (pin "2") (pinfunction "2_2") (pintype "passive"))
    )
    (net (code "27") (name "Net-(APD1-PadA)") (class "Default")
      (node (ref "APD1") (pin "A") (pinfunction "A_A") (pintype "passive"))
      (node (ref "R21") (pin "2") (pinfunction "2_2") (pintype "passive"))
    )
    (net (code "28") (name "Net-(APD2-PadA)") (class "Default")
      (node (ref "APD2") (pin "A") (pinfunction "A_A") (pintype "passive"))
      (node (ref "R22") (pin "2") (pinfunction "2_2") (pintype "passive"))
    )
    (net (code "29") (name "Net-(APD3-PadA)") (class "Default")
      (node (ref "APD3") (pin "A") (pinfunction "A_A") (pintype "passive"))
      (node (ref "R23") (pin "2") (pinfunction "2_2") (pintype "passive"))
    )
    (net (code "30") (name "Net-(APD4-PadA)") (class "Default")
      (node (ref "APD4") (pin "A") (pinfunction "A_A") (pintype "passive"))
      (node (ref "R24") (pin "2") (pinfunction "2_2") (pintype "passive"))
    )
    (net (code "31") (name "Net-(BAL-1)") (class "Default")
      (node (ref "BAL") (pin "P$1") (pinfunction "1_P$1") (pintype "bidirectional"))
      (node (ref "TRX2") (pin "ANTN") (pinfunction "ANTN_ANTN") (pintype "bidirectional"))
    )
    (net (code "32") (name "Net-(BAL-3)") (class "Default")
      (node (ref "BAL") (pin "P$3") (pinfunction "3_P$3") (pintype "bidirectional"))
      (node (ref "TRX2") (pin "ANTP") (pinfunction "ANTP_ANTP") (pintype "bidirectional"))
    )
    (net (code "33") (name "Net-(BAL-4)") (class "Default")
      (node (ref "BAL") (pin "P$4") (pinfunction "4_P$4") (pintype "bidirectional"))
      (node (ref "C16") (pin "2") (pinfunction "2_2") (pintype "passive"))
      (node (ref "C19") (pin "1") (pinfunction "1_1") (pintype "passive"))
      (node (ref "L2") (pin "1") (pinfunction "1_1") (pintype "passive"))
    )
    (net (code "34") (name "Net-(C16-Pad1)") (class "Default")
      (node (ref "C16") (pin "1") (pinfunction "1_1") (pintype "passive"))
      (node (ref "L1") (pin "2") (pinfunction "2_2") (pintype "passive"))
    )
    (net (code "35") (name "Net-(C41-Pad2)") (class "Default")
      (node (ref "C41") (pin "2") (pinfunction "2_2") (pintype "passive"))
      (node (ref "R33") (pin "1") (pinfunction "1_1") (pintype "passive"))
    )
    (net (code "36") (name "Net-(C42-Pad1)") (class "Default")
      (node (ref "C42") (pin "1") (pinfunction "1_1") (pintype "passive"))
      (node (ref "C45") (pin "1") (pinfunction "1_1") (pintype "passive"))
      (node (ref "R33") (pin "2") (pinfunction "2_2") (pintype "passive"))
    )
    (net (code "37") (name "Net-(C43-Pad1)") (class "Default")
      (node (ref "C43") (pin "1") (pinfunction "1_1") (pintype "passive"))
      (node (ref "R27") (pin "2") (pinfunction "2_2") (pintype "passive"))
      (node (ref "R28") (pin "1") (pinfunction "1_1") (pintype "passive"))
    )
    (net (code "38") (name "Net-(C44-Pad1)") (class "Default")
      (node (ref "C44") (pin "1") (pinfunction "1_1") (pintype "passive"))
      (node (ref "R28") (pin "2") (pinfunction "2_2") (pintype "passive"))
      (node (ref "R29") (pin "1") (pinfunction "1_1") (pintype "passive"))
    )
    (net (code "39") (name "Net-(IC2-PCINT2{slash}ADC2_PA2)") (class "Default")
      (node (ref "IC2") (pin "38") (pinfunction "PCINT2/ADC2_PA2_38") (pintype "bidirectional"))
      (node (ref "R38") (pin "1") (pinfunction "1_1") (pintype "passive"))
    )
    (net (code "40") (name "Net-(IC2-PCINT7{slash}ADC7_PA7)") (class "Default")
      (node (ref "IC2") (pin "33") (pinfunction "PCINT7/ADC7_PA7_33") (pintype "bidirectional"))
      (node (ref "R39") (pin "1") (pinfunction "1_1") (pintype "passive"))
    )
    (net (code "41") (name "Net-(L3-Pad1)") (class "Default")
      (node (ref "L3") (pin "1") (pinfunction "1_1") (pintype "passive"))
      (node (ref "TRX2") (pin "L1") (pinfunction "L1_L1") (pintype "bidirectional"))
    )
    (net (code "42") (name "Net-(L3-Pad2)") (class "Default")
      (node (ref "L3") (pin "2") (pinfunction "2_2") (pintype "passive"))
      (node (ref "TRX2") (pin "L2") (pinfunction "L2_L2") (pintype "bidirectional"))
    )
    (net (code "43") (name "Net-(MCU_SF-D+{slash}RF4)") (class "Default")
      (node (ref "MCU_SF") (pin "14") (pinfunction "D+/RF4_14") (pintype "bidirectional"))
      (node (ref "R1") (pin "2") (pinfunction "2_2") (pintype "passive"))
    )
    (net (code "44") (name "Net-(MCU_SF-D-{slash}RF3)") (class "Default")
      (node (ref "MCU_SF") (pin "15") (pinfunction "D-/RF3_15") (pintype "bidirectional"))
      (node (ref "R2") (pin "2") (pinfunction "2_2") (pintype "passive"))
    )
    (net (code "45") (name "Net-(MCU_SF-VCAP)") (class "Default")
      (node (ref "C18") (pin "1") (pinfunction "1_1") (pintype "passive"))
      (node (ref "MCU_SF") (pin "10") (pinfunction "VCAP_10") (pintype "bidirectional"))
    )
    (net (code "46") (name "Net-(MOS1-D1)") (class "Default")
      (node (ref "MOS1") (pin "6") (pinfunction "D1_6") (pintype "input"))
      (node (ref "OCP1") (pin "7") (pinfunction "SENSE_7") (pintype "bidirectional"))
      (node (ref "R10") (pin "2") (pinfunction "2_2") (pintype "passive"))
    )
    (net (code "47") (name "Net-(MOS1-G1)") (class "Default")
      (node (ref "MOS1") (pin "2") (pinfunction "G1_2") (pintype "input"))
      (node (ref "OCP1") (pin "6") (pinfunction "GATE_6") (pintype "bidirectional"))
    )
    (net (code "48") (name "Net-(MOS2-D1)") (class "Default")
      (node (ref "MOS2") (pin "6") (pinfunction "D1_6") (pintype "input"))
      (node (ref "OCP2") (pin "7") (pinfunction "SENSE_7") (pintype "bidirectional"))
      (node (ref "R18") (pin "2") (pinfunction "2_2") (pintype "passive"))
    )
    (net (code "49") (name "Net-(MOS2-G1)") (class "Default")
      (node (ref "MOS2") (pin "2") (pinfunction "G1_2") (pintype "input"))
      (node (ref "OCP2") (pin "6") (pinfunction "GATE_6") (pintype "bidirectional"))
    )
    (net (code "50") (name "Net-(OCP1-ON)") (class "Default")
      (node (ref "JP4") (pin "1") (pinfunction "1_1") (pintype "passive"))
      (node (ref "OCP1") (pin "4") (pinfunction "ON_4") (pintype "bidirectional"))
      (node (ref "Q1") (pin "3") (pinfunction "C_3") (pintype "passive"))
      (node (ref "R14") (pin "1") (pinfunction "1_1") (pintype "passive"))
    )
    (net (code "51") (name "Net-(OCP2-ON)") (class "Default")
      (node (ref "JP3") (pin "1") (pinfunction "1_1") (pintype "passive"))
      (node (ref "OCP2") (pin "4") (pinfunction "ON_4") (pintype "bidirectional"))
      (node (ref "Q2") (pin "3") (pinfunction "C_3") (pintype "passive"))
      (node (ref "Q3") (pin "3") (pinfunction "C_3") (pintype "passive"))
      (node (ref "R20") (pin "1") (pinfunction "1_1") (pintype "passive"))
    )
    (net (code "52") (name "Net-(OPAMP1A-+IN)") (class "Default")
      (node (ref "C42") (pin "2") (pinfunction "2_2") (pintype "passive"))
      (node (ref "OPAMP1") (pin "3") (pinfunction "+IN_3") (pintype "input"))
      (node (ref "R34") (pin "1") (pinfunction "1_1") (pintype "passive"))
    )
    (net (code "53") (name "Net-(OPAMP1A--IN)") (class "Default")
      (node (ref "OPAMP1") (pin "2") (pinfunction "-IN_2") (pintype "input"))
      (node (ref "R35") (pin "2") (pinfunction "2_2") (pintype "passive"))
      (node (ref "R37") (pin "1") (pinfunction "1_1") (pintype "passive"))
    )
    (net (code "54") (name "Net-(OPAMPB-+IN)") (class "Default")
      (node (ref "OPAMP") (pin "5") (pinfunction "+IN_5") (pintype "input"))
      (node (ref "R25") (pin "2") (pinfunction "2_2") (pintype "passive"))
      (node (ref "R30") (pin "2") (pinfunction "2_2") (pintype "passive"))
    )
    (net (code "55") (name "Net-(R6-Pad1)") (class "Default")
      (node (ref "R6") (pin "1") (pinfunction "1_1") (pintype "passive"))
      (node (ref "SFD1") (pin "A") (pinfunction "A_A") (pintype "passive"))
    )
    (net (code "56") (name "Net-(R7-Pad1)") (class "Default")
      (node (ref "R7") (pin "1") (pinfunction "1_1") (pintype "passive"))
      (node (ref "SFD2") (pin "A") (pinfunction "A_A") (pintype "passive"))
    )
    (net (code "57") (name "Net-(R32-CW)") (class "Default")
      (node (ref "R29") (pin "2") (pinfunction "2_2") (pintype "passive"))
      (node (ref "R32") (pin "3") (pinfunction "CW_3") (pintype "passive"))
    )
    (net (code "58") (name "Net-(R32-WIPER)") (class "Default")
      (node (ref "C41") (pin "1") (pinfunction "1_1") (pintype "passive"))
      (node (ref "R32") (pin "2") (pinfunction "WIPER_2") (pintype "passive"))
    )
    (net (code "59") (name "Net-(TCXO-OUT)") (class "Default")
      (node (ref "C28") (pin "1") (pinfunction "1_1") (pintype "passive"))
      (node (ref "TCXO") (pin "P$3") (pinfunction "OUT_P$3") (pintype "output"))
    )
    (net (code "60") (name "Net-(TRX2-VDDANA2)") (class "Default")
      (node (ref "C20") (pin "1") (pinfunction "1_1") (pintype "passive"))
      (node (ref "TRX2") (pin "VDD_ANA2") (pinfunction "VDDANA2_VDD_ANA2") (pintype "bidirectional"))
    )
    (net (code "61") (name "Net-(TRX2-VDD_ANA1)") (class "Default")
      (node (ref "C17") (pin "1") (pinfunction "1_1") (pintype "passive"))
      (node (ref "TRX2") (pin "VDD_ANA") (pinfunction "VDD_ANA1_VDD_ANA") (pintype "bidirectional"))
    )
    (net (code "62") (name "OSC1") (class "Default")
      (node (ref "C6") (pin "1") (pinfunction "1_1") (pintype "passive"))
      (node (ref "MCU_SF") (pin "40") (pinfunction "OSC2/CLKO/RP6/RA6_40") (pintype "bidirectional"))
      (node (ref "XTAL1") (pin "1") (pinfunction "1_1") (pintype "passive"))
    )
    (net (code "63") (name "OSC2") (class "Default")
      (node (ref "C7") (pin "1") (pinfunction "1_1") (pintype "passive"))
      (node (ref "MCU_SF") (pin "39") (pinfunction "OSC1/CLKI/RP10/RA7_39") (pintype "bidirectional"))
      (node (ref "XTAL1") (pin "2") (pinfunction "2_2") (pintype "passive"))
    )
    (net (code "64") (name "PA1") (class "Default")
      (node (ref "IC2") (pin "39") (pinfunction "PCINT1/ADC1_PA1_39") (pintype "bidirectional"))
      (node (ref "R17") (pin "2") (pinfunction "2_2") (pintype "passive"))
      (node (ref "R19") (pin "1") (pinfunction "1_1") (pintype "passive"))
    )
    (net (code "65") (name "PD0_RXA") (class "Default")
      (node (ref "IC2") (pin "14") (pinfunction "PCINT24/RXD0_PD0_14") (pintype "bidirectional"))
      (node (ref "JP1") (pin "P$7") (pinfunction "P$7_P$7") (pintype "bidirectional"))
    )
    (net (code "66") (name "PD1_TXA") (class "Default")
      (node (ref "IC2") (pin "15") (pinfunction "PCINT25/TXD0_PD1_15") (pintype "bidirectional"))
      (node (ref "JP1") (pin "P$5") (pinfunction "P$5_P$5") (pintype "bidirectional"))
    )
    (net (code "67") (name "PGC") (class "Default")
      (node (ref "JP1") (pin "P$17") (pinfunction "P$17_P$17") (pintype "bidirectional"))
      (node (ref "JP2") (pin "1") (pinfunction "1_1") (pintype "passive"))
      (node (ref "MCU_SF") (pin "42") (pinfunction "CTED5/PGC/RB6_42") (pintype "bidirectional"))
    )
    (net (code "68") (name "PGD") (class "Default")
      (node (ref "JP1") (pin "P$15") (pinfunction "P$15_P$15") (pintype "bidirectional"))
      (node (ref "JP2") (pin "2") (pinfunction "2_2") (pintype "passive"))
      (node (ref "MCU_SF") (pin "37") (pinfunction "CTED6/PGD/RB7_37") (pintype "bidirectional"))
    )
    (net (code "69") (name "RSSI") (class "Default")
      (node (ref "JP1") (pin "P$4") (pinfunction "P$4_P$4") (pintype "bidirectional"))
      (node (ref "MCU_SF") (pin "27") (pinfunction "SEG15/AN4/LVDIN/C1INA/C2INA/C3INA/RP5/RA5_27") (pintype "bidirectional"))
      (node (ref "TRX1") (pin "P$11") (pinfunction "RSSI_P$11") (pintype "bidirectional"))
    )
    (net (code "70") (name "SFWARD_3V3_2") (class "Default")
      (node (ref "74LVC1G125") (pin "5") (pinfunction "VCC_5") (pintype "power_in"))
      (node (ref "C1") (pin "2") (pinfunction "2_2") (pintype "passive"))
      (node (ref "C13") (pin "2") (pinfunction "2_2") (pintype "passive"))
      (node (ref "C2") (pin "2") (pinfunction "2_2") (pintype "passive"))
      (node (ref "C21") (pin "1") (pinfunction "1_1") (pintype "passive"))
      (node (ref "C22") (pin "1") (pinfunction "1_1") (pintype "passive"))
      (node (ref "C23") (pin "1") (pinfunction "1_1") (pintype "passive"))
      (node (ref "C24") (pin "1") (pinfunction "1_1") (pintype "passive"))
      (node (ref "C25") (pin "1") (pinfunction "1_1") (pintype "passive"))
      (node (ref "C26") (pin "1") (pinfunction "1_1") (pintype "passive"))
      (node (ref "C27") (pin "1") (pinfunction "1_1") (pintype "passive"))
      (node (ref "FM_SF") (pin "2") (pinfunction "VCC_2") (pintype "input"))
      (node (ref "JP1") (pin "P$9") (pinfunction "P$9_P$9") (pintype "bidirectional"))
      (node (ref "MCU_SF") (pin "17") (pinfunction "VUSB3V3_17") (pintype "bidirectional"))
      (node (ref "MCU_SF") (pin "19") (pinfunction "AVDD_19") (pintype "bidirectional"))
      (node (ref "MCU_SF") (pin "26") (pinfunction "VDD_1_26") (pintype "bidirectional"))
      (node (ref "MCU_SF") (pin "38") (pinfunction "VDD_2_38") (pintype "bidirectional"))
      (node (ref "MCU_SF") (pin "57") (pinfunction "VDD_3_57") (pintype "bidirectional"))
      (node (ref "MOS1") (pin "1") (pinfunction "S1_1") (pintype "input"))
      (node (ref "OCP1") (pin "3") (pinfunction "OUT_3") (pintype "bidirectional"))
      (node (ref "R11") (pin "1") (pinfunction "1_1") (pintype "passive"))
      (node (ref "R12") (pin "1") (pinfunction "1_1") (pintype "passive"))
      (node (ref "R13") (pin "1") (pinfunction "1_1") (pintype "passive"))
      (node (ref "R3") (pin "1") (pinfunction "1_1") (pintype "passive"))
      (node (ref "R4") (pin "1") (pinfunction "1_1") (pintype "passive"))
      (node (ref "R5") (pin "1") (pinfunction "1_1") (pintype "passive"))
      (node (ref "R6") (pin "2") (pinfunction "2_2") (pintype "passive"))
      (node (ref "R8") (pin "1") (pinfunction "1_1") (pintype "passive"))
      (node (ref "R9") (pin "1") (pinfunction "1_1") (pintype "passive"))
      (node (ref "TRX2") (pin "VDD_IO") (pinfunction "VDD_IO_VDD_IO") (pintype "bidirectional"))
      (node (ref "U2") (pin "5") (pinfunction "VCC_5") (pintype "power_in"))
    )
    (net (code "71") (name "SPI_FM_CS") (class "Default")
      (node (ref "FM_SF") (pin "7") (pinfunction "S#_7") (pintype "input"))
      (node (ref "MCU_SF") (pin "22") (pinfunction "SEG21/VREF-/AN2/RP2/RA2_22") (pintype "bidirectional"))
      (node (ref "R9") (pin "2") (pinfunction "2_2") (pintype "passive"))
    )
    (net (code "72") (name "SPI_MISO") (class "Default")
      (node (ref "FM_SF") (pin "8") (pinfunction "DQ1_8") (pintype "input"))
      (node (ref "MCU_SF") (pin "23") (pinfunction "SEG18/AN1/RP1/RA1_23") (pintype "bidirectional"))
      (node (ref "R5") (pin "2") (pinfunction "2_2") (pintype "passive"))
    )
    (net (code "73") (name "SPI_MOSI") (class "Default")
      (node (ref "FM_SF") (pin "15") (pinfunction "DQ0_15") (pintype "input"))
      (node (ref "MCU_SF") (pin "24") (pinfunction "SEG19/AN0/AN1-/RP0/RA0_24") (pintype "bidirectional"))
      (node (ref "R8") (pin "2") (pinfunction "2_2") (pintype "passive"))
    )
    (net (code "74") (name "SPI_SCK") (class "Default")
      (node (ref "FM_SF") (pin "16") (pinfunction "C_16") (pintype "input"))
      (node (ref "MCU_SF") (pin "21") (pinfunction "VREF+/AN3/RP3/RA3_21") (pintype "bidirectional"))
      (node (ref "R11") (pin "2") (pinfunction "2_2") (pintype "passive"))
    )
    (net (code "75") (name "SUP_3V3_1") (class "Default")
      (node (ref "JP2") (pin "49") (pinfunction "49_49") (pintype "passive"))
      (node (ref "JP2") (pin "50") (pinfunction "50_50") (pintype "passive"))
    )
    (net (code "76") (name "SUP_3V3_2") (class "Default")
      (node (ref "JP2") (pin "25") (pinfunction "25_25") (pintype "passive"))
      (node (ref "JP2") (pin "26") (pinfunction "26_26") (pintype "passive"))
      (node (ref "OCP1") (pin "8") (pinfunction "IN_8") (pintype "bidirectional"))
      (node (ref "R10") (pin "1") (pinfunction "1_1") (pintype "passive"))
      (node (ref "R14") (pin "2") (pinfunction "2_2") (pintype "passive"))
    )
    (net (code "77") (name "SUP_5V0") (class "Default")
      (node (ref "JP2") (pin "15") (pinfunction "15_15") (pintype "passive"))
      (node (ref "JP2") (pin "16") (pinfunction "16_16") (pintype "passive"))
      (node (ref "OCP2") (pin "8") (pinfunction "IN_8") (pintype "bidirectional"))
      (node (ref "R18") (pin "1") (pinfunction "1_1") (pintype "passive"))
      (node (ref "R20") (pin "2") (pinfunction "2_2") (pintype "passive"))
    )
    (net (code "78") (name "TCXO_EN2") (class "Default")
      (node (ref "TCXO") (pin "P$4") (pinfunction "VCC_P$4") (pintype "power_in"))
      (node (ref "TRX2") (pin "TCXO_EN") (pinfunction "TCXO_EN_TCXO_EN") (pintype "bidirectional"))
    )
    (net (code "79") (name "TRX1") (class "Default")
      (node (ref "MMCX_908_222101T") (pin "P$1") (pinfunction "SGNL_P$1") (pintype "bidirectional"))
      (node (ref "TRX1") (pin "P$2") (pinfunction "ANT_P$2") (pintype "bidirectional"))
    )
    (net (code "80") (name "TRX1_AFOUT") (class "Default")
      (node (ref "C38") (pin "2") (pinfunction "2_2") (pintype "passive"))
      (node (ref "JP1") (pin "P$6") (pinfunction "P$6_P$6") (pintype "bidirectional"))
      (node (ref "TRX1") (pin "P$13") (pinfunction "AF_P$13") (pintype "bidirectional"))
    )
    (net (code "81") (name "TRX1_RXSELECT") (class "Default")
      (node (ref "IC2") (pin "1") (pinfunction "PCINT8/XCK0/T0_PB0_1") (pintype "bidirectional"))
      (node (ref "OPAMP") (pin "6") (pinfunction "-IN_6") (pintype "input"))
      (node (ref "R21") (pin "1") (pinfunction "1_1") (pintype "passive"))
      (node (ref "R36") (pin "1") (pinfunction "1_1") (pintype "passive"))
      (node (ref "TRX1") (pin "P$16") (pinfunction "RXSELECT_P$16") (pintype "bidirectional"))
    )
    (net (code "82") (name "TRX1_TXD") (class "Default")
      (node (ref "JP1") (pin "P$8") (pinfunction "P$8_P$8") (pintype "bidirectional"))
      (node (ref "OPAMP1") (pin "1") (pinfunction "OUT_1") (pintype "output"))
      (node (ref "R35") (pin "1") (pinfunction "1_1") (pintype "passive"))
      (node (ref "TRX1") (pin "P$14") (pinfunction "TXD_P$14") (pintype "bidirectional"))
    )
    (net (code "83") (name "TRX1_TXSELECT") (class "Default")
      (node (ref "JP1") (pin "P$10") (pinfunction "P$10_P$10") (pintype "bidirectional"))
      (node (ref "OPAMP") (pin "7") (pinfunction "OUT_7") (pintype "output"))
      (node (ref "TRX1") (pin "P$15") (pinfunction "TXSELECT_P$15") (pintype "bidirectional"))
    )
    (net (code "84") (name "TRX1{slash}TRX2") (class "Default")
      (node (ref "MCU_SF") (pin "46") (pinfunction "SEG9/RP14/CTED1/RB2_46") (pintype "bidirectional"))
    )
    (net (code "85") (name "TRX2_CS") (class "Default")
      (node (ref "MCU_SF") (pin "64") (pinfunction "LCDBIAS3/RP30/C_64") (pintype "bidirectional"))
    )
    (net (code "86") (name "TRX2_MOSI") (class "Default")
      (node (ref "JP1") (pin "P$12") (pinfunction "P$12_P$12") (pintype "bidirectional"))
      (node (ref "MCU_SF") (pin "60") (pinfunction "COM3/RP34/RE6_60") (pintype "bidirectional"))
      (node (ref "TRX2") (pin "MOSI") (pinfunction "MOSI_MOSI") (pintype "bidirectional"))
    )
    (net (code "87") (name "TRX2_RX{slash}TX") (class "Default")
      (node (ref "MCU_SF") (pin "47") (pinfunction "VLCAP2/RP9/RB1_47") (pintype "bidirectional"))
    )
    (net (code "88") (name "TRX2_TX{slash}RX") (class "Default")
      (node (ref "MCU_SF") (pin "48") (pinfunction "VLCAP1/RP8/CTED13/INT0/RB0_48") (pintype "bidirectional"))
    )
    (net (code "89") (name "unconnected-(FM_SF-DNU(1)-Pad4)") (class "Default")
      (node (ref "FM_SF") (pin "4") (pinfunction "DNU(1)_4") (pintype "input"))
    )
    (net (code "90") (name "unconnected-(FM_SF-DNU(2)-Pad5)") (class "Default")
      (node (ref "FM_SF") (pin "5") (pinfunction "DNU(2)_5") (pintype "input"))
    )
    (net (code "91") (name "unconnected-(FM_SF-DNU(3)-Pad6)") (class "Default")
      (node (ref "FM_SF") (pin "6") (pinfunction "DNU(3)_6") (pintype "input"))
    )
    (net (code "92") (name "unconnected-(FM_SF-DNU(4)-Pad11)") (class "Default")
      (node (ref "FM_SF") (pin "11") (pinfunction "DNU(4)_11") (pintype "input"))
    )
    (net (code "93") (name "unconnected-(FM_SF-DNU(5)-Pad12)") (class "Default")
      (node (ref "FM_SF") (pin "12") (pinfunction "DNU(5)_12") (pintype "input"))
    )
    (net (code "94") (name "unconnected-(FM_SF-DNU(6)-Pad13)") (class "Default")
      (node (ref "FM_SF") (pin "13") (pinfunction "DNU(6)_13") (pintype "input"))
    )
    (net (code "95") (name "unconnected-(FM_SF-DNU(7)-Pad14)") (class "Default")
      (node (ref "FM_SF") (pin "14") (pinfunction "DNU(7)_14") (pintype "input"))
    )
    (net (code "96") (name "unconnected-(IC2-PCINT3{slash}ADC3_PA3-Pad37)") (class "Default")
      (node (ref "IC2") (pin "37") (pinfunction "PCINT3/ADC3_PA3_37") (pintype "bidirectional"))
    )
    (net (code "97") (name "unconnected-(IC2-PCINT4{slash}ADC4_PA4-Pad36)") (class "Default")
      (node (ref "IC2") (pin "36") (pinfunction "PCINT4/ADC4_PA4_36") (pintype "bidirectional"))
    )
    (net (code "98") (name "unconnected-(IC2-PCINT5{slash}ADC5_PA5-Pad35)") (class "Default")
      (node (ref "IC2") (pin "35") (pinfunction "PCINT5/ADC5_PA5_35") (pintype "bidirectional"))
    )
    (net (code "99") (name "unconnected-(IC2-PCINT6{slash}ADC6_PA6-Pad34)") (class "Default")
      (node (ref "IC2") (pin "34") (pinfunction "PCINT6/ADC6_PA6_34") (pintype "bidirectional"))
    )
    (net (code "100") (name "unconnected-(IC2-PCINT12{slash}OC0B{slash}SS_PB4-Pad5)") (class "Default")
      (node (ref "IC2") (pin "5") (pinfunction "PCINT12/OC0B/SS_PB4_5") (pintype "bidirectional"))
    )
    (net (code "101") (name "unconnected-(IC2-PCINT13{slash}MOSI_PB5-Pad6)") (class "Default")
      (node (ref "IC2") (pin "6") (pinfunction "PCINT13/MOSI_PB5_6") (pintype "bidirectional"))
    )
    (net (code "102") (name "unconnected-(IC2-PCINT14{slash}MISO_PB6-Pad7)") (class "Default")
      (node (ref "IC2") (pin "7") (pinfunction "PCINT14/MISO_PB6_7") (pintype "bidirectional"))
    )
    (net (code "103") (name "unconnected-(IC2-PCINT15{slash}SCK_PB7-Pad8)") (class "Default")
      (node (ref "IC2") (pin "8") (pinfunction "PCINT15/SCK_PB7_8") (pintype "bidirectional"))
    )
    (net (code "104") (name "unconnected-(IC2-PCINT16{slash}SCL_PC0-Pad22)") (class "Default")
      (node (ref "IC2") (pin "22") (pinfunction "PCINT16/SCL_PC0_22") (pintype "bidirectional"))
    )
    (net (code "105") (name "unconnected-(IC2-PCINT17{slash}SDA_PC1-Pad23)") (class "Default")
      (node (ref "IC2") (pin "23") (pinfunction "PCINT17/SDA_PC1_23") (pintype "bidirectional"))
    )
    (net (code "106") (name "unconnected-(IC2-PCINT18{slash}TCK_PC2-Pad24)") (class "Default")
      (node (ref "IC2") (pin "24") (pinfunction "PCINT18/TCK_PC2_24") (pintype "bidirectional"))
    )
    (net (code "107") (name "unconnected-(IC2-PCINT19{slash}TMS_PC3-Pad25)") (class "Default")
      (node (ref "IC2") (pin "25") (pinfunction "PCINT19/TMS_PC3_25") (pintype "bidirectional"))
    )
    (net (code "108") (name "unconnected-(IC2-PCINT20{slash}TDO_PC4-Pad26)") (class "Default")
      (node (ref "IC2") (pin "26") (pinfunction "PCINT20/TDO_PC4_26") (pintype "bidirectional"))
    )
    (net (code "109") (name "unconnected-(IC2-PCINT21{slash}TDI_PC5-Pad27)") (class "Default")
      (node (ref "IC2") (pin "27") (pinfunction "PCINT21/TDI_PC5_27") (pintype "bidirectional"))
    )
    (net (code "110") (name "unconnected-(IC2-PCINT22{slash}TOSC1_PC6-Pad28)") (class "Default")
      (node (ref "IC2") (pin "28") (pinfunction "PCINT22/TOSC1_PC6_28") (pintype "bidirectional"))
    )
    (net (code "111") (name "unconnected-(IC2-PCINT23{slash}TOSC2_PC7-Pad29)") (class "Default")
      (node (ref "IC2") (pin "29") (pinfunction "PCINT23/TOSC2_PC7_29") (pintype "bidirectional"))
    )
    (net (code "112") (name "unconnected-(IC2-PCINT28{slash}OC1B_PD4-Pad18)") (class "Default")
      (node (ref "IC2") (pin "18") (pinfunction "PCINT28/OC1B_PD4_18") (pintype "bidirectional"))
    )
    (net (code "113") (name "unconnected-(IC2-PCINT30{slash}OC2B{slash}ICP_PD6-Pad20)") (class "Default")
      (node (ref "IC2") (pin "20") (pinfunction "PCINT30/OC2B/ICP_PD6_20") (pintype "bidirectional"))
    )
    (net (code "114") (name "unconnected-(IC2-PCINT31{slash}OC2A_PD7-Pad21)") (class "Default")
      (node (ref "IC2") (pin "21") (pinfunction "PCINT31/OC2A_PD7_21") (pintype "bidirectional"))
    )
    (net (code "115") (name "unconnected-(IC2-~{RESET}-Pad9)") (class "Default")
      (node (ref "IC2") (pin "9") (pinfunction "~{RESET}_9") (pintype "input"))
    )
    (net (code "116") (name "unconnected-(JP1-PadP$18)") (class "Default")
      (node (ref "JP1") (pin "P$18") (pinfunction "P$18_P$18") (pintype "bidirectional"))
    )
    (net (code "117") (name "unconnected-(JP1-PadP$20)") (class "Default")
      (node (ref "JP1") (pin "P$20") (pinfunction "P$20_P$20") (pintype "bidirectional"))
    )
    (net (code "118") (name "unconnected-(JP1-PadP$21)") (class "Default")
      (node (ref "JP1") (pin "P$21") (pinfunction "P$21_P$21") (pintype "bidirectional"))
    )
    (net (code "119") (name "unconnected-(JP1-PadP$22)") (class "Default")
      (node (ref "JP1") (pin "P$22") (pinfunction "P$22_P$22") (pintype "bidirectional"))
    )
    (net (code "120") (name "unconnected-(JP1-PadP$23)") (class "Default")
      (node (ref "JP1") (pin "P$23") (pinfunction "P$23_P$23") (pintype "bidirectional"))
    )
    (net (code "121") (name "unconnected-(JP1-PadP$24)") (class "Default")
      (node (ref "JP1") (pin "P$24") (pinfunction "P$24_P$24") (pintype "bidirectional"))
    )
    (net (code "122") (name "unconnected-(JP2-Pad4)") (class "Default")
      (node (ref "JP2") (pin "4") (pinfunction "4_4") (pintype "passive"))
    )
    (net (code "123") (name "unconnected-(JP2-Pad5)") (class "Default")
      (node (ref "JP2") (pin "5") (pinfunction "5_5") (pintype "passive"))
    )
    (net (code "124") (name "unconnected-(JP2-Pad6)") (class "Default")
      (node (ref "JP2") (pin "6") (pinfunction "6_6") (pintype "passive"))
    )
    (net (code "125") (name "unconnected-(JP2-Pad7)") (class "Default")
      (node (ref "JP2") (pin "7") (pinfunction "7_7") (pintype "passive"))
    )
    (net (code "126") (name "unconnected-(JP2-Pad8)") (class "Default")
      (node (ref "JP2") (pin "8") (pinfunction "8_8") (pintype "passive"))
    )
    (net (code "127") (name "unconnected-(JP2-Pad9)") (class "Default")
      (node (ref "JP2") (pin "9") (pinfunction "9_9") (pintype "passive"))
    )
    (net (code "128") (name "unconnected-(JP2-Pad10)") (class "Default")
      (node (ref "JP2") (pin "10") (pinfunction "10_10") (pintype "passive"))
    )
    (net (code "129") (name "unconnected-(JP2-Pad17)") (class "Default")
      (node (ref "JP2") (pin "17") (pinfunction "17_17") (pintype "passive"))
    )
    (net (code "130") (name "unconnected-(JP2-Pad18)") (class "Default")
      (node (ref "JP2") (pin "18") (pinfunction "18_18") (pintype "passive"))
    )
    (net (code "131") (name "unconnected-(JP2-Pad19)") (class "Default")
      (node (ref "JP2") (pin "19") (pinfunction "19_19") (pintype "passive"))
    )
    (net (code "132") (name "unconnected-(JP2-Pad20)") (class "Default")
      (node (ref "JP2") (pin "20") (pinfunction "20_20") (pintype "passive"))
    )
    (net (code "133") (name "unconnected-(JP2-Pad21)") (class "Default")
      (node (ref "JP2") (pin "21") (pinfunction "21_21") (pintype "passive"))
    )
    (net (code "134") (name "unconnected-(JP2-Pad22)") (class "Default")
      (node (ref "JP2") (pin "22") (pinfunction "22_22") (pintype "passive"))
    )
    (net (code "135") (name "unconnected-(JP2-Pad23)") (class "Default")
      (node (ref "JP2") (pin "23") (pinfunction "23_23") (pintype "passive"))
    )
    (net (code "136") (name "unconnected-(JP2-Pad24)") (class "Default")
      (node (ref "JP2") (pin "24") (pinfunction "24_24") (pintype "passive"))
    )
    (net (code "137") (name "unconnected-(JP2-Pad27)") (class "Default")
      (node (ref "JP2") (pin "27") (pinfunction "27_27") (pintype "passive"))
    )
    (net (code "138") (name "unconnected-(JP2-Pad28)") (class "Default")
      (node (ref "JP2") (pin "28") (pinfunction "28_28") (pintype "passive"))
    )
    (net (code "139") (name "unconnected-(JP2-Pad29)") (class "Default")
      (node (ref "JP2") (pin "29") (pinfunction "29_29") (pintype "passive"))
    )
    (net (code "140") (name "unconnected-(JP2-Pad30)") (class "Default")
      (node (ref "JP2") (pin "30") (pinfunction "30_30") (pintype "passive"))
    )
    (net (code "141") (name "unconnected-(JP2-Pad31)") (class "Default")
      (node (ref "JP2") (pin "31") (pinfunction "31_31") (pintype "passive"))
    )
    (net (code "142") (name "unconnected-(JP2-Pad32)") (class "Default")
      (node (ref "JP2") (pin "32") (pinfunction "32_32") (pintype "passive"))
    )
    (net (code "143") (name "unconnected-(JP2-Pad33)") (class "Default")
      (node (ref "JP2") (pin "33") (pinfunction "33_33") (pintype "passive"))
    )
    (net (code "144") (name "unconnected-(JP2-Pad34)") (class "Default")
      (node (ref "JP2") (pin "34") (pinfunction "34_34") (pintype "passive"))
    )
    (net (code "145") (name "unconnected-(JP2-Pad35)") (class "Default")
      (node (ref "JP2") (pin "35") (pinfunction "35_35") (pintype "passive"))
    )
    (net (code "146") (name "unconnected-(JP2-Pad36)") (class "Default")
      (node (ref "JP2") (pin "36") (pinfunction "36_36") (pintype "passive"))
    )
    (net (code "147") (name "unconnected-(JP2-Pad37)") (class "Default")
      (node (ref "JP2") (pin "37") (pinfunction "37_37") (pintype "passive"))
    )
    (net (code "148") (name "unconnected-(JP2-Pad38)") (class "Default")
      (node (ref "JP2") (pin "38") (pinfunction "38_38") (pintype "passive"))
    )
    (net (code "149") (name "unconnected-(JP2-Pad39)") (class "Default")
      (node (ref "JP2") (pin "39") (pinfunction "39_39") (pintype "passive"))
    )
    (net (code "150") (name "unconnected-(JP2-Pad40)") (class "Default")
      (node (ref "JP2") (pin "40") (pinfunction "40_40") (pintype "passive"))
    )
    (net (code "151") (name "unconnected-(JP2-Pad41)") (class "Default")
      (node (ref "JP2") (pin "41") (pinfunction "41_41") (pintype "passive"))
    )
    (net (code "152") (name "unconnected-(JP2-Pad42)") (class "Default")
      (node (ref "JP2") (pin "42") (pinfunction "42_42") (pintype "passive"))
    )
    (net (code "153") (name "unconnected-(JP2-Pad45)") (class "Default")
      (node (ref "JP2") (pin "45") (pinfunction "45_45") (pintype "passive"))
    )
    (net (code "154") (name "unconnected-(JP2-Pad46)") (class "Default")
      (node (ref "JP2") (pin "46") (pinfunction "46_46") (pintype "passive"))
    )
    (net (code "155") (name "unconnected-(JP2-Pad47)") (class "Default")
      (node (ref "JP2") (pin "47") (pinfunction "47_47") (pintype "passive"))
    )
    (net (code "156") (name "unconnected-(JP2-Pad48)") (class "Default")
      (node (ref "JP2") (pin "48") (pinfunction "48_48") (pintype "passive"))
    )
    (net (code "157") (name "unconnected-(MCU_SF-COM0{slash}RP33{slash}REFO1{slash}RE3-Pad63)") (class "Default")
      (node (ref "MCU_SF") (pin "63") (pinfunction "COM0/RP33/REFO1/RE3_63") (pintype "bidirectional"))
    )
    (net (code "158") (name "unconnected-(MCU_SF-COM1{slash}RP32{slash}RE4-Pad62)") (class "Default")
      (node (ref "MCU_SF") (pin "62") (pinfunction "COM1/RP32/RE4_62") (pintype "bidirectional"))
    )
    (net (code "159") (name "unconnected-(MCU_SF-COM2{slash}RP37{slash}RE5-Pad61)") (class "Default")
      (node (ref "MCU_SF") (pin "61") (pinfunction "COM2/RP37/RE5_61") (pintype "bidirectional"))
    )
    (net (code "160") (name "unconnected-(MCU_SF-COM5{slash}SEG29{slash}AN19{slash}RP39{slash}RG1-Pad4)") (class "Default")
      (node (ref "MCU_SF") (pin "4") (pinfunction "COM5/SEG29/AN19/RP39/RG1_4") (pintype "bidirectional"))
    )
    (net (code "161") (name "unconnected-(MCU_SF-COM6{slash}SEG30{slash}AN18{slash}C3INA{slash}RP42{slash}RG2-Pad5)") (class "Default")
      (node (ref "MCU_SF") (pin "5") (pinfunction "COM6/SEG30/AN18/C3INA/RP42/RG2_5") (pintype "bidirectional"))
    )
    (net (code "162") (name "unconnected-(MCU_SF-COM7{slash}SEG31{slash}AN17{slash}C3INB{slash}RP43{slash}RG3-Pad6)") (class "Default")
      (node (ref "MCU_SF") (pin "6") (pinfunction "COM7/SEG31/AN17/C3INB/RP43/RG3_6") (pintype "bidirectional"))
    )
    (net (code "163") (name "unconnected-(MCU_SF-LCDBIAS0{slash}RP31{slash}RE7-Pad59)") (class "Default")
      (node (ref "MCU_SF") (pin "59") (pinfunction "LCDBIAS0/RP31/RE7_59") (pintype "bidirectional"))
    )
    (net (code "164") (name "unconnected-(MCU_SF-SEG0{slash}RP20{slash}PSP0{slash}RD0-Pad58)") (class "Default")
      (node (ref "MCU_SF") (pin "58") (pinfunction "SEG0/RP20/PSP0/RD0_58") (pintype "bidirectional"))
    )
    (net (code "165") (name "unconnected-(MCU_SF-SEG1{slash}RP21{slash}PSP1{slash}RD1-Pad55)") (class "Default")
      (node (ref "MCU_SF") (pin "55") (pinfunction "SEG1/RP21/PSP1/RD1_55") (pintype "bidirectional"))
    )
    (net (code "166") (name "unconnected-(MCU_SF-SEG2{slash}RP22{slash}PSP2{slash}RD2-Pad54)") (class "Default")
      (node (ref "MCU_SF") (pin "54") (pinfunction "SEG2/RP22/PSP2/RD2_54") (pintype "bidirectional"))
    )
    (net (code "167") (name "unconnected-(MCU_SF-SEG3{slash}RP23{slash}PSP3{slash}RD3-Pad53)") (class "Default")
      (node (ref "MCU_SF") (pin "53") (pinfunction "SEG3/RP23/PSP3/RD3_53") (pintype "bidirectional"))
    )
    (net (code "168") (name "unconnected-(MCU_SF-SEG4{slash}RP24{slash}PSP4{slash}RD4-Pad52)") (class "Default")
      (node (ref "MCU_SF") (pin "52") (pinfunction "SEG4/RP24/PSP4/RD4_52") (pintype "bidirectional"))
    )
    (net (code "169") (name "unconnected-(MCU_SF-SEG5{slash}SDA2{slash}RP25{slash}PSP5{slash}RD5-Pad51)") (class "Default")
      (node (ref "MCU_SF") (pin "51") (pinfunction "SEG5/SDA2/RP25/PSP5/RD5_51") (pintype "bidirectional"))
    )
    (net (code "170") (name "unconnected-(MCU_SF-SEG6{slash}SCL2{slash}RP26{slash}PSP6{slash}RD6-Pad50)") (class "Default")
      (node (ref "MCU_SF") (pin "50") (pinfunction "SEG6/SCL2/RP26/PSP6/RD6_50") (pintype "bidirectional"))
    )
    (net (code "171") (name "unconnected-(MCU_SF-SEG7{slash}RP27{slash}REFO2{slash}PSP7{slash}RD7-Pad49)") (class "Default")
      (node (ref "MCU_SF") (pin "49") (pinfunction "SEG7/RP27/REFO2/PSP7/RD7_49") (pintype "bidirectional"))
    )
    (net (code "172") (name "unconnected-(MCU_SF-SEG8{slash}RP13{slash}CTED4{slash}RB5-Pad43)") (class "Default")
      (node (ref "MCU_SF") (pin "43") (pinfunction "SEG8/RP13/CTED4/RB5_43") (pintype "bidirectional"))
    )
    (net (code "173") (name "unconnected-(MCU_SF-SEG10{slash}RP7{slash}CTED2{slash}RB3-Pad45)") (class "Default")
      (node (ref "MCU_SF") (pin "45") (pinfunction "SEG10/RP7/CTED2/RB3_45") (pintype "bidirectional"))
    )
    (net (code "174") (name "unconnected-(MCU_SF-SEG11{slash}RP12{slash}CTED3{slash}RB4-Pad44)") (class "Default")
      (node (ref "MCU_SF") (pin "44") (pinfunction "SEG11/RP12/CTED3/RB4_44") (pintype "bidirectional"))
    )
    (net (code "175") (name "unconnected-(MCU_SF-SEG12{slash}RP16{slash}CTED10{slash}RC5-Pad36)") (class "Default")
      (node (ref "MCU_SF") (pin "36") (pinfunction "SEG12/RP16/CTED10/RC5_36") (pintype "bidirectional"))
    )
    (net (code "176") (name "unconnected-(MCU_SF-SEG13{slash}AN9{slash}RP11{slash}CTED7{slash}RC2-Pad33)") (class "Default")
      (node (ref "MCU_SF") (pin "33") (pinfunction "SEG13/AN9/RP11/CTED7/RC2_33") (pintype "bidirectional"))
    )
    (net (code "177") (name "unconnected-(MCU_SF-SEG14{slash}AN6{slash}RP4{slash}RA4-Pad28)") (class "Default")
      (node (ref "MCU_SF") (pin "28") (pinfunction "SEG14/AN6/RP4/RA4_28") (pintype "bidirectional"))
    )
    (net (code "178") (name "unconnected-(MCU_SF-SEG16{slash}SDA1{slash}RP17{slash}CTED9{slash}RC4-Pad35)") (class "Default")
      (node (ref "MCU_SF") (pin "35") (pinfunction "SEG16/SDA1/RP17/CTED9/RC4_35") (pintype "bidirectional"))
    )
    (net (code "179") (name "unconnected-(MCU_SF-SEG17{slash}SCL1{slash}RP15{slash}CTED8{slash}RC3-Pad34)") (class "Default")
      (node (ref "MCU_SF") (pin "34") (pinfunction "SEG17/SCL1/RP15/CTED8/RC3_34") (pintype "bidirectional"))
    )
    (net (code "180") (name "unconnected-(MCU_SF-SEG20{slash}AN7{slash}CTMUI{slash}C2INB{slash}RP36{slash}RF2-Pad16)") (class "Default")
      (node (ref "MCU_SF") (pin "16") (pinfunction "SEG20/AN7/CTMUI/C2INB/RP36/RF2_16") (pintype "bidirectional"))
    )
    (net (code "181") (name "unconnected-(MCU_SF-SEG23{slash}CVREF{slash}AN10{slash}C1INB{slash}RP35{slash}RF5-Pad13)") (class "Default")
      (node (ref "MCU_SF") (pin "13") (pinfunction "SEG23/CVREF/AN10/C1INB/RP35/RF5_13") (pintype "bidirectional"))
    )
    (net (code "182") (name "unconnected-(MCU_SF-SEG24{slash}AN11{slash}C1INA{slash}RP40{slash}RF6-Pad12)") (class "Default")
      (node (ref "MCU_SF") (pin "12") (pinfunction "SEG24/AN11/C1INA/RP40/RF6_12") (pintype "bidirectional"))
    )
    (net (code "183") (name "unconnected-(MCU_SF-SEG25{slash}AN5{slash}RP38{slash}RF7-Pad11)") (class "Default")
      (node (ref "MCU_SF") (pin "11") (pinfunction "SEG25/AN5/RP38/RF7_11") (pintype "bidirectional"))
    )
    (net (code "184") (name "unconnected-(MCU_SF-SEG26{slash}AN16{slash}C3INC{slash}RP44{slash}RTCC{slash}RG4-Pad8)") (class "Default")
      (node (ref "MCU_SF") (pin "8") (pinfunction "SEG26/AN16/C3INC/RP44/RTCC/RG4_8") (pintype "bidirectional"))
    )
    (net (code "185") (name "unconnected-(MCU_SF-SOSCI{slash}RC1-Pad29)") (class "Default")
      (node (ref "MCU_SF") (pin "29") (pinfunction "SOSCI/RC1_29") (pintype "bidirectional"))
    )
    (net (code "186") (name "unconnected-(MCU_SF-SOSCO{slash}SCLKI{slash}PWRLCLK{slash}RC0-Pad30)") (class "Default")
      (node (ref "MCU_SF") (pin "30") (pinfunction "SOSCO/SCLKI/PWRLCLK/RC0_30") (pintype "bidirectional"))
    )
    (net (code "187") (name "unconnected-(MCU_SF-VBAT-Pad18)") (class "Default")
      (node (ref "MCU_SF") (pin "18") (pinfunction "VBAT_18") (pintype "bidirectional"))
    )
    (net (code "188") (name "unconnected-(MOS1-D2-Pad3)") (class "Default")
      (node (ref "MOS1") (pin "3") (pinfunction "D2_3") (pintype "input"))
    )
    (net (code "189") (name "unconnected-(MOS1-G2-Pad5)") (class "Default")
      (node (ref "MOS1") (pin "5") (pinfunction "G2_5") (pintype "input"))
    )
    (net (code "190") (name "unconnected-(MOS1-S2-Pad4)") (class "Default")
      (node (ref "MOS1") (pin "4") (pinfunction "S2_4") (pintype "input"))
    )
    (net (code "191") (name "unconnected-(MOS2-D2-Pad3)") (class "Default")
      (node (ref "MOS2") (pin "3") (pinfunction "D2_3") (pintype "input"))
    )
    (net (code "192") (name "unconnected-(MOS2-G2-Pad5)") (class "Default")
      (node (ref "MOS2") (pin "5") (pinfunction "G2_5") (pintype "input"))
    )
    (net (code "193") (name "unconnected-(MOS2-S2-Pad4)") (class "Default")
      (node (ref "MOS2") (pin "4") (pinfunction "S2_4") (pintype "input"))
    )
    (net (code "194") (name "unconnected-(OCP1-GATEP-Pad2)") (class "Default")
      (node (ref "OCP1") (pin "2") (pinfunction "GATEP_2") (pintype "bidirectional"))
    )
    (net (code "195") (name "unconnected-(OCP1-PWRGD-Pad5)") (class "Default")
      (node (ref "OCP1") (pin "5") (pinfunction "PWRGD_5") (pintype "bidirectional"))
    )
    (net (code "196") (name "unconnected-(OCP2-GATEP-Pad2)") (class "Default")
      (node (ref "OCP2") (pin "2") (pinfunction "GATEP_2") (pintype "bidirectional"))
    )
    (net (code "197") (name "unconnected-(OCP2-PWRGD-Pad5)") (class "Default")
      (node (ref "OCP2") (pin "5") (pinfunction "PWRGD_5") (pintype "bidirectional"))
    )
    (net (code "198") (name "unconnected-(TRX1-NC1-PadP$4)") (class "Default")
      (node (ref "TRX1") (pin "P$4") (pinfunction "NC1_P$4") (pintype "bidirectional"))
    )
    (net (code "199") (name "unconnected-(TRX1-NC2-PadP$5)") (class "Default")
      (node (ref "TRX1") (pin "P$5") (pinfunction "NC2_P$5") (pintype "bidirectional"))
    )
    (net (code "200") (name "unconnected-(TRX1-NC3-PadP$6)") (class "Default")
      (node (ref "TRX1") (pin "P$6") (pinfunction "NC3_P$6") (pintype "bidirectional"))
    )
    (net (code "201") (name "unconnected-(TRX1-NC4-PadP$7)") (class "Default")
      (node (ref "TRX1") (pin "P$7") (pinfunction "NC4_P$7") (pintype "bidirectional"))
    )
    (net (code "202") (name "unconnected-(TRX1-NC5-PadP$8)") (class "Default")
      (node (ref "TRX1") (pin "P$8") (pinfunction "NC5_P$8") (pintype "bidirectional"))
    )
    (net (code "203") (name "unconnected-(TRX1-RXD-PadP$12)") (class "Default")
      (node (ref "TRX1") (pin "P$12") (pinfunction "RXD_P$12") (pintype "bidirectional"))
    )
    (net (code "204") (name "unconnected-(TRX2-PadCLK)") (class "Default")
      (node (ref "TRX2") (pin "CLK") (pinfunction "CLK_CLK") (pintype "bidirectional"))
    )
    (net (code "205") (name "unconnected-(TRX2-PadCLK16N)") (class "Default")
      (node (ref "TRX2") (pin "CLK16N") (pinfunction "CLK16N_CLK16N") (pintype "bidirectional"))
    )
    (net (code "206") (name "unconnected-(TRX2-PadFILT)") (class "Default")
      (node (ref "TRX2") (pin "FILT") (pinfunction "FILT_FILT") (pintype "bidirectional"))
    )
    (net (code "207") (name "unconnected-(TRX2-PadIRQ)") (class "Default")
      (node (ref "TRX2") (pin "IRQ") (pinfunction "IRQ_IRQ") (pintype "bidirectional"))
    )
    (net (code "208") (name "unconnected-(TRX2-PadMISO)") (class "Default")
      (node (ref "TRX2") (pin "MISO") (pinfunction "MISO_MISO") (pintype "bidirectional"))
    )
    (net (code "209") (name "unconnected-(TRX2-PadSEL)") (class "Default")
      (node (ref "TRX2") (pin "SEL") (pinfunction "SEL_SEL") (pintype "bidirectional"))
    )
    (net (code "210") (name "unconnected-(TRX2-PadSYSCLK)") (class "Default")
      (node (ref "TRX2") (pin "SYSCLK") (pinfunction "SYSCLK_SYSCLK") (pintype "bidirectional"))
    )
  )
)
